# disciples_v1.net
KiCad netlist of a schematic drawn in EAGLE
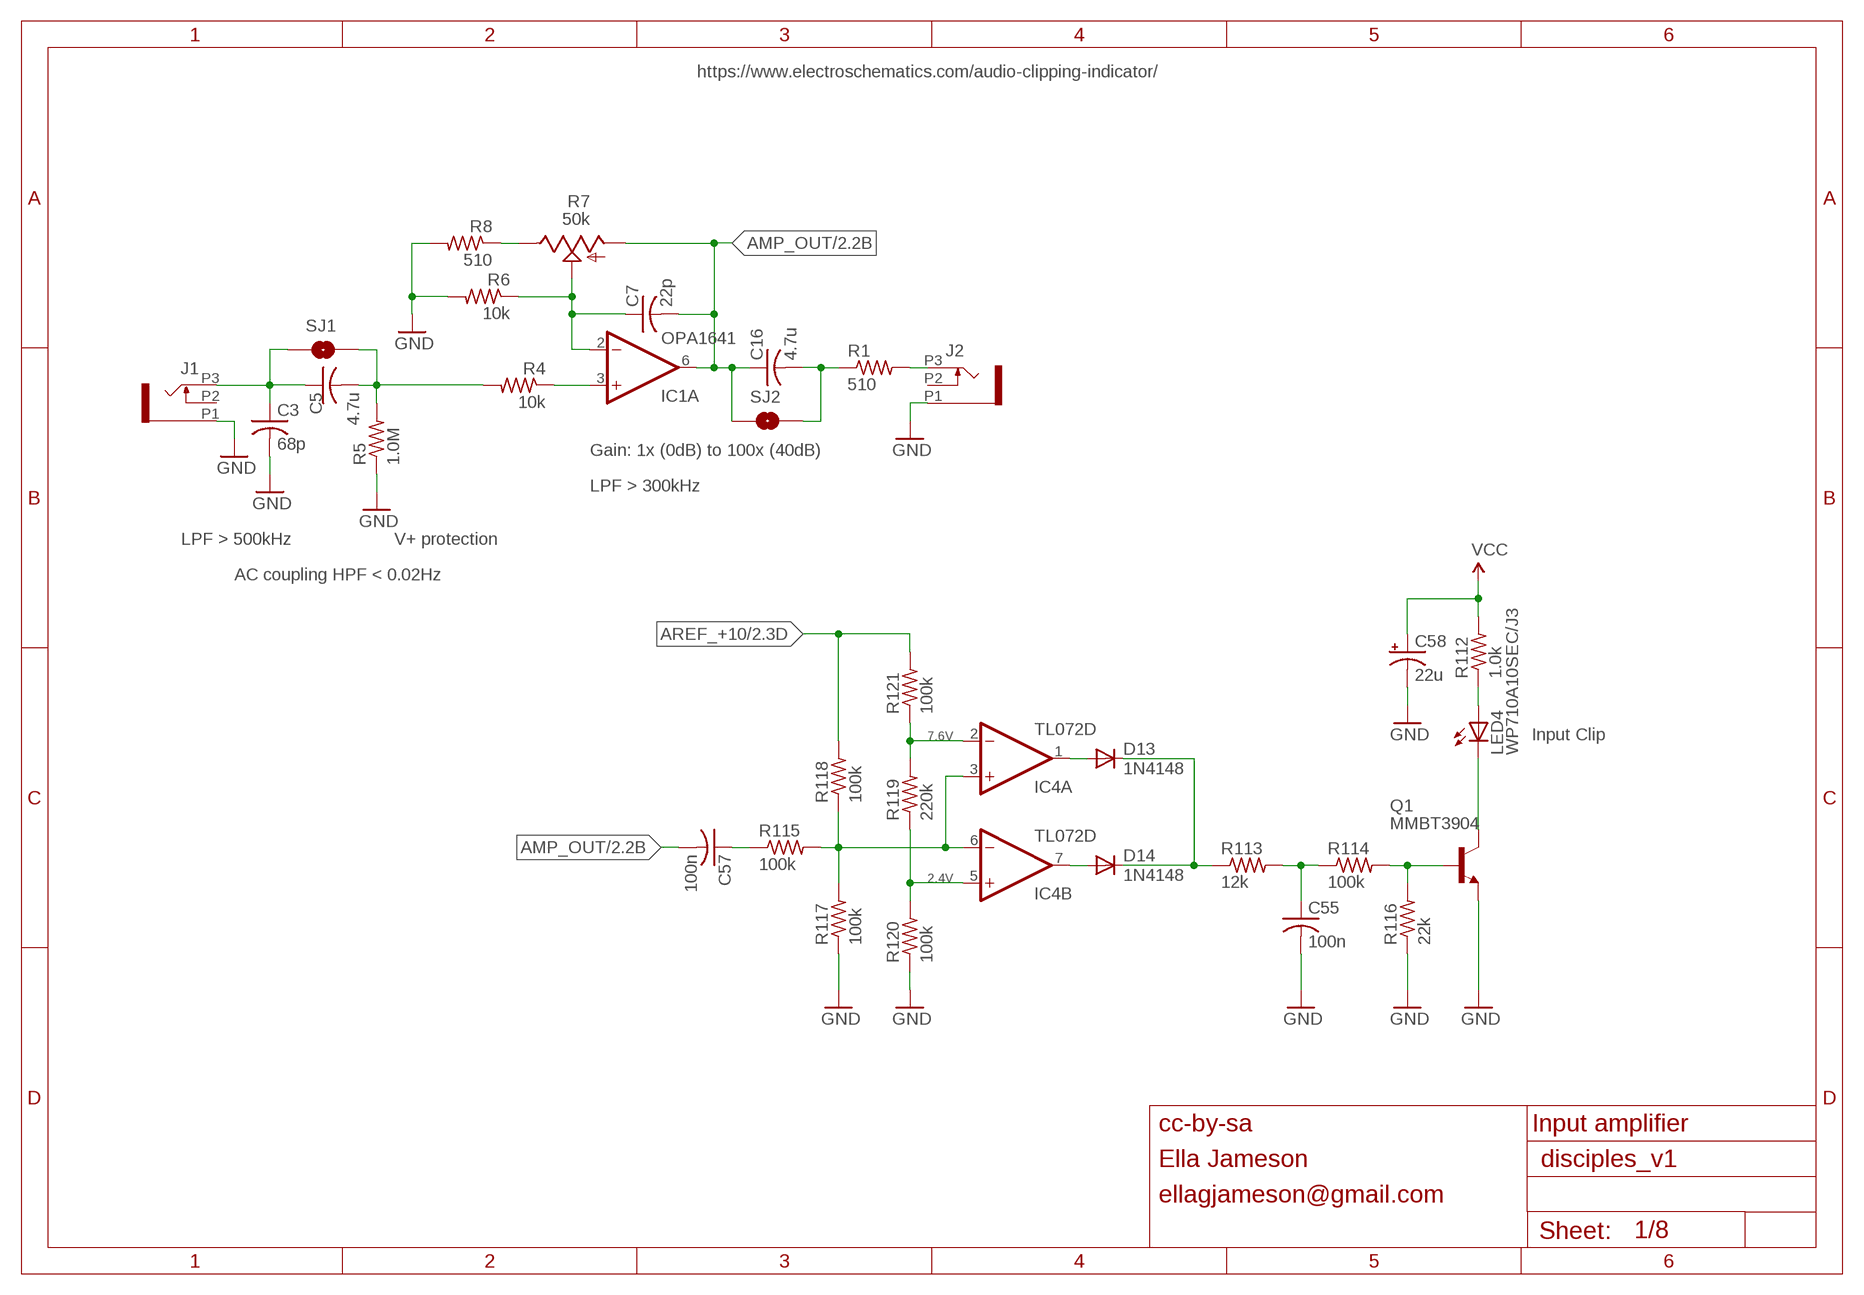
[diagram p0: schematic, sheet 1]
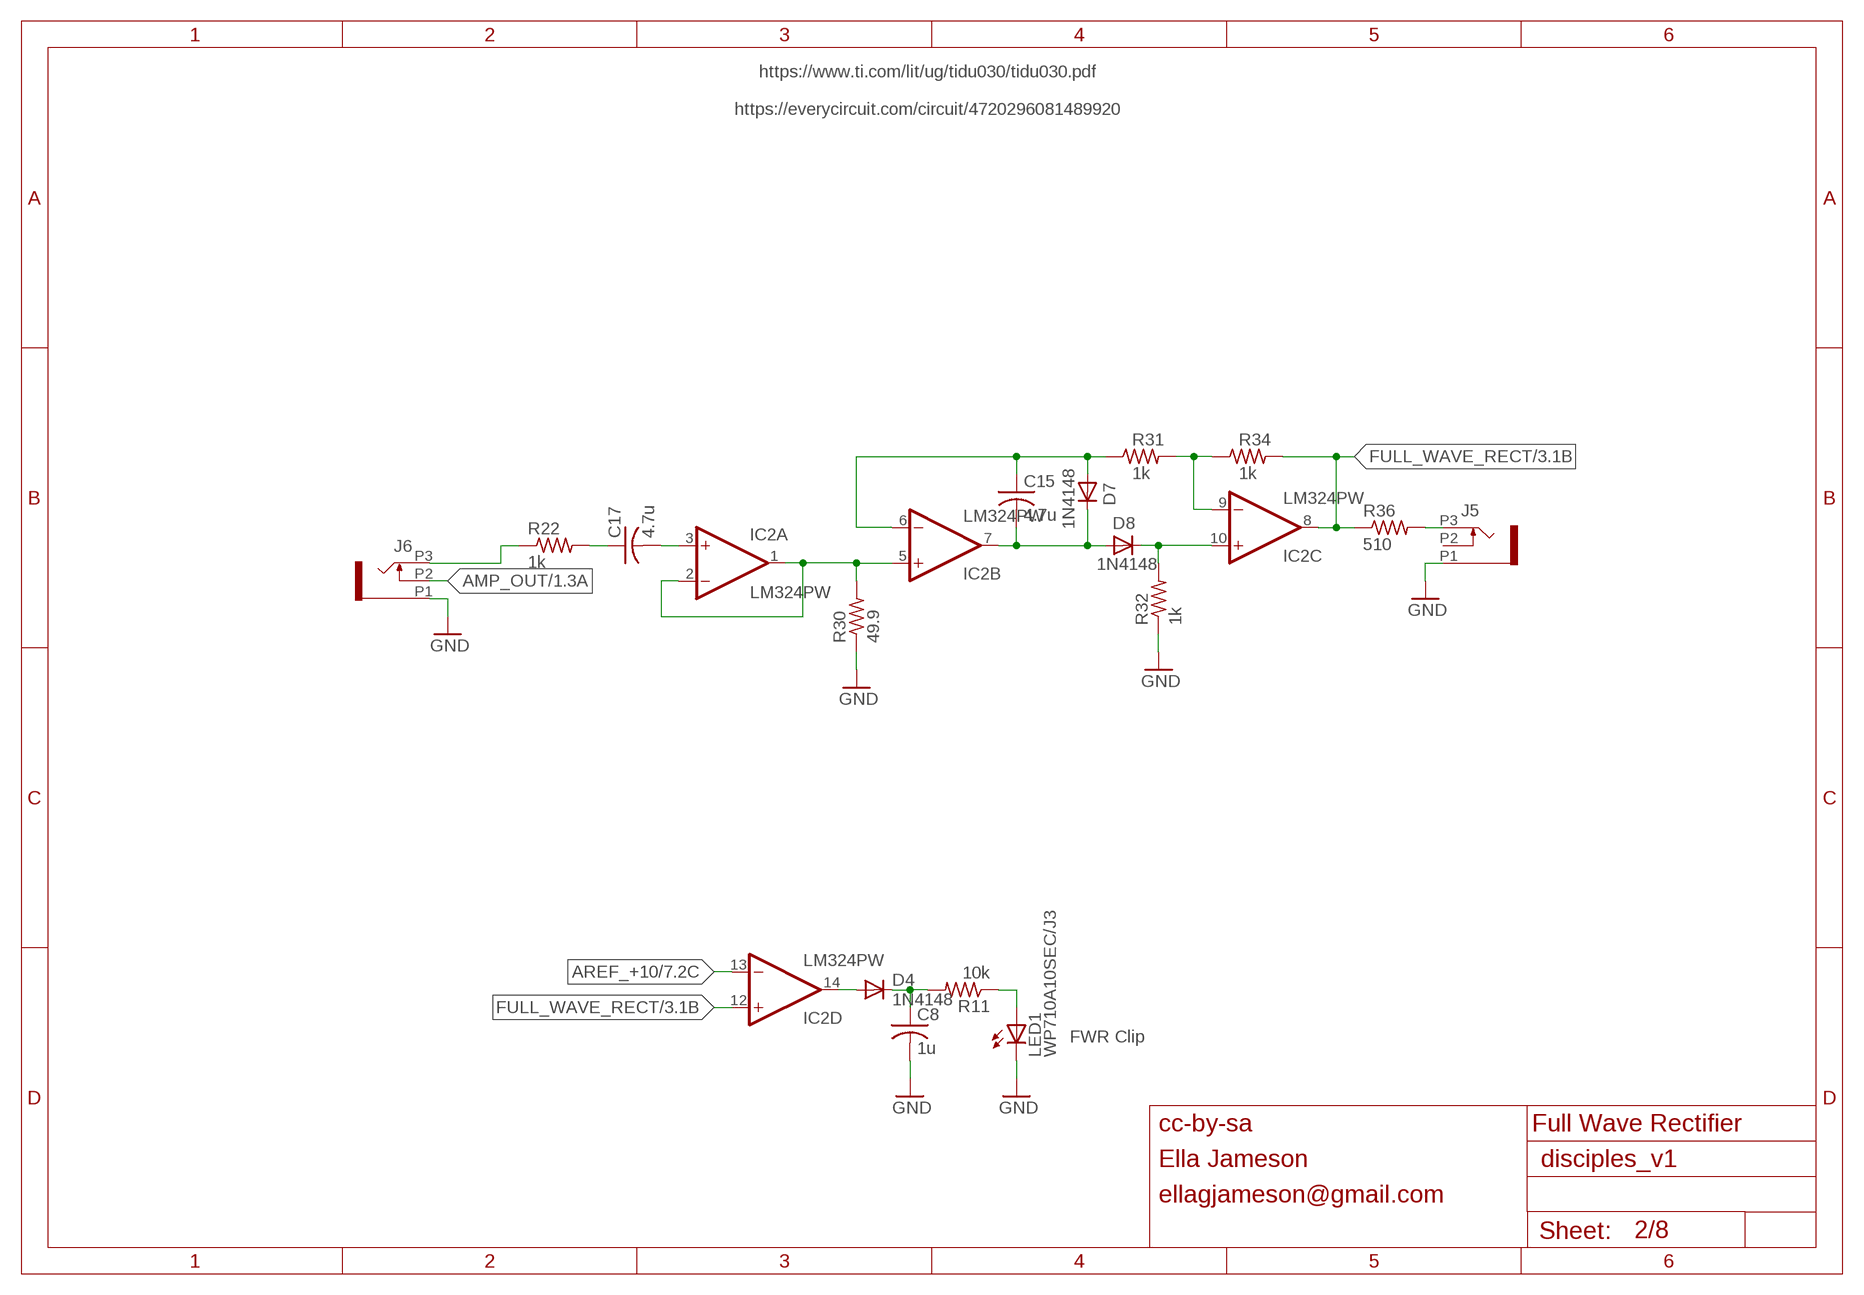
[diagram p1: schematic, sheet 2]
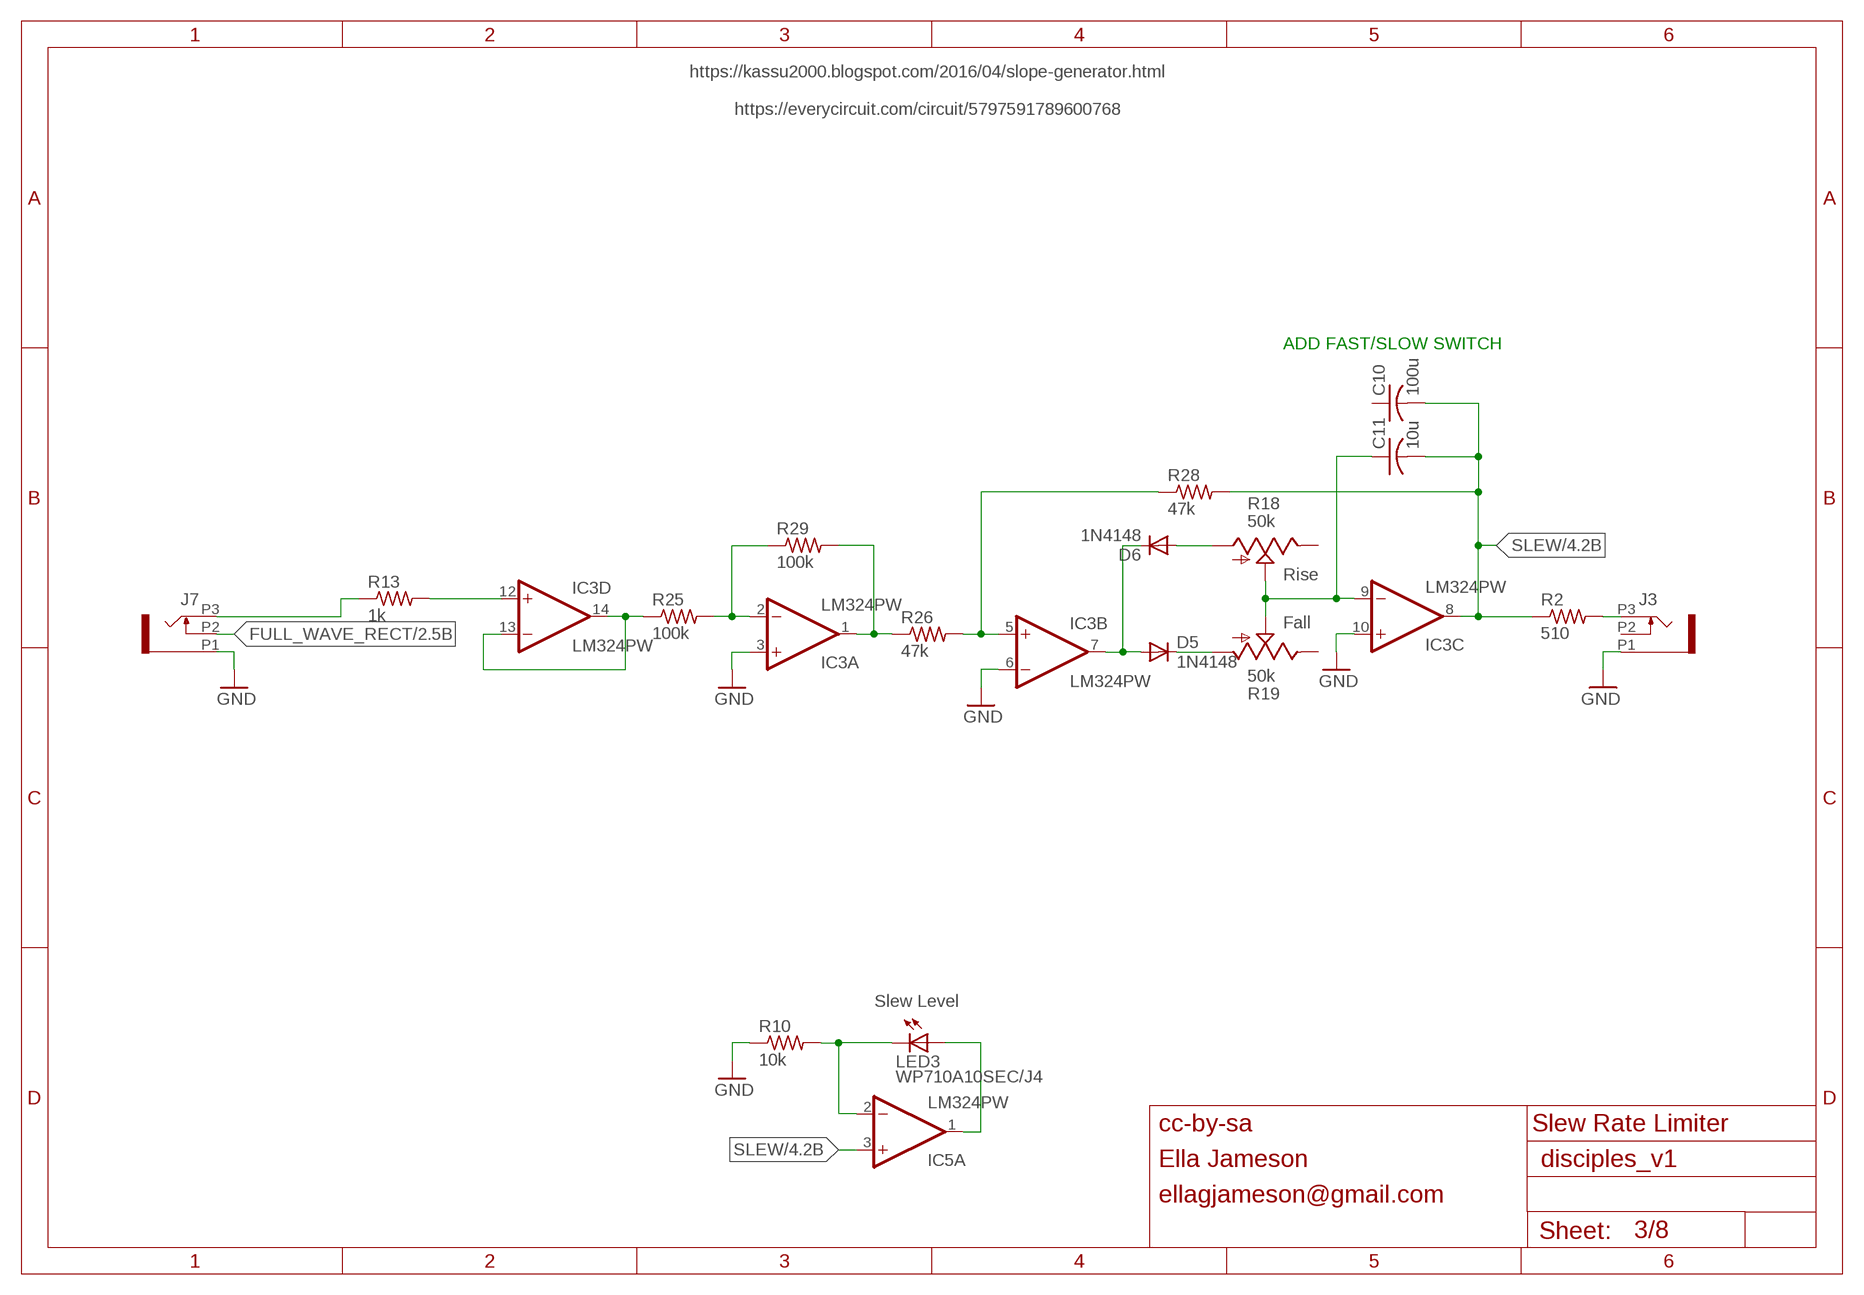
[diagram p2: schematic, sheet 3]
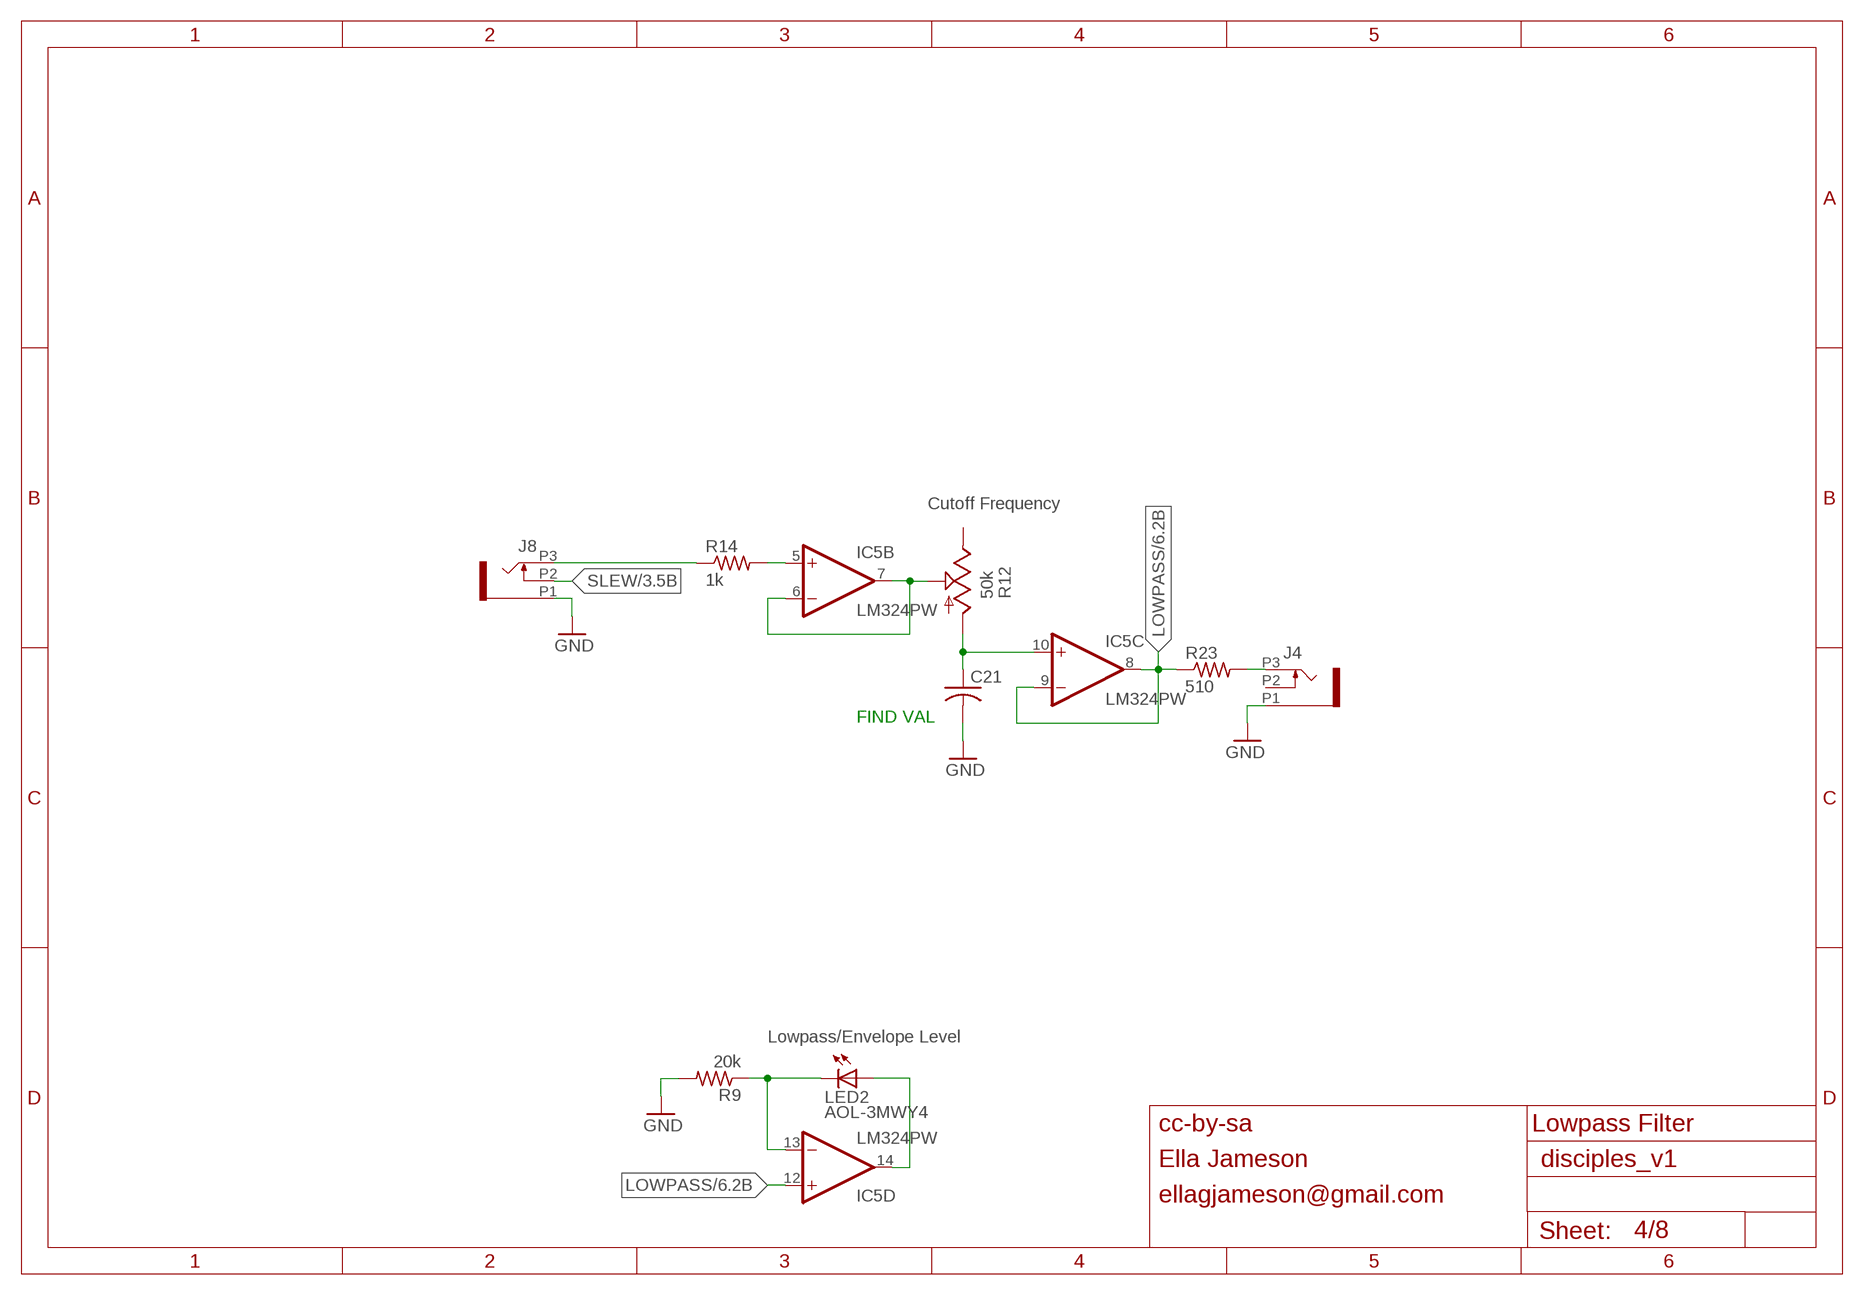
[diagram p3: schematic, sheet 4]
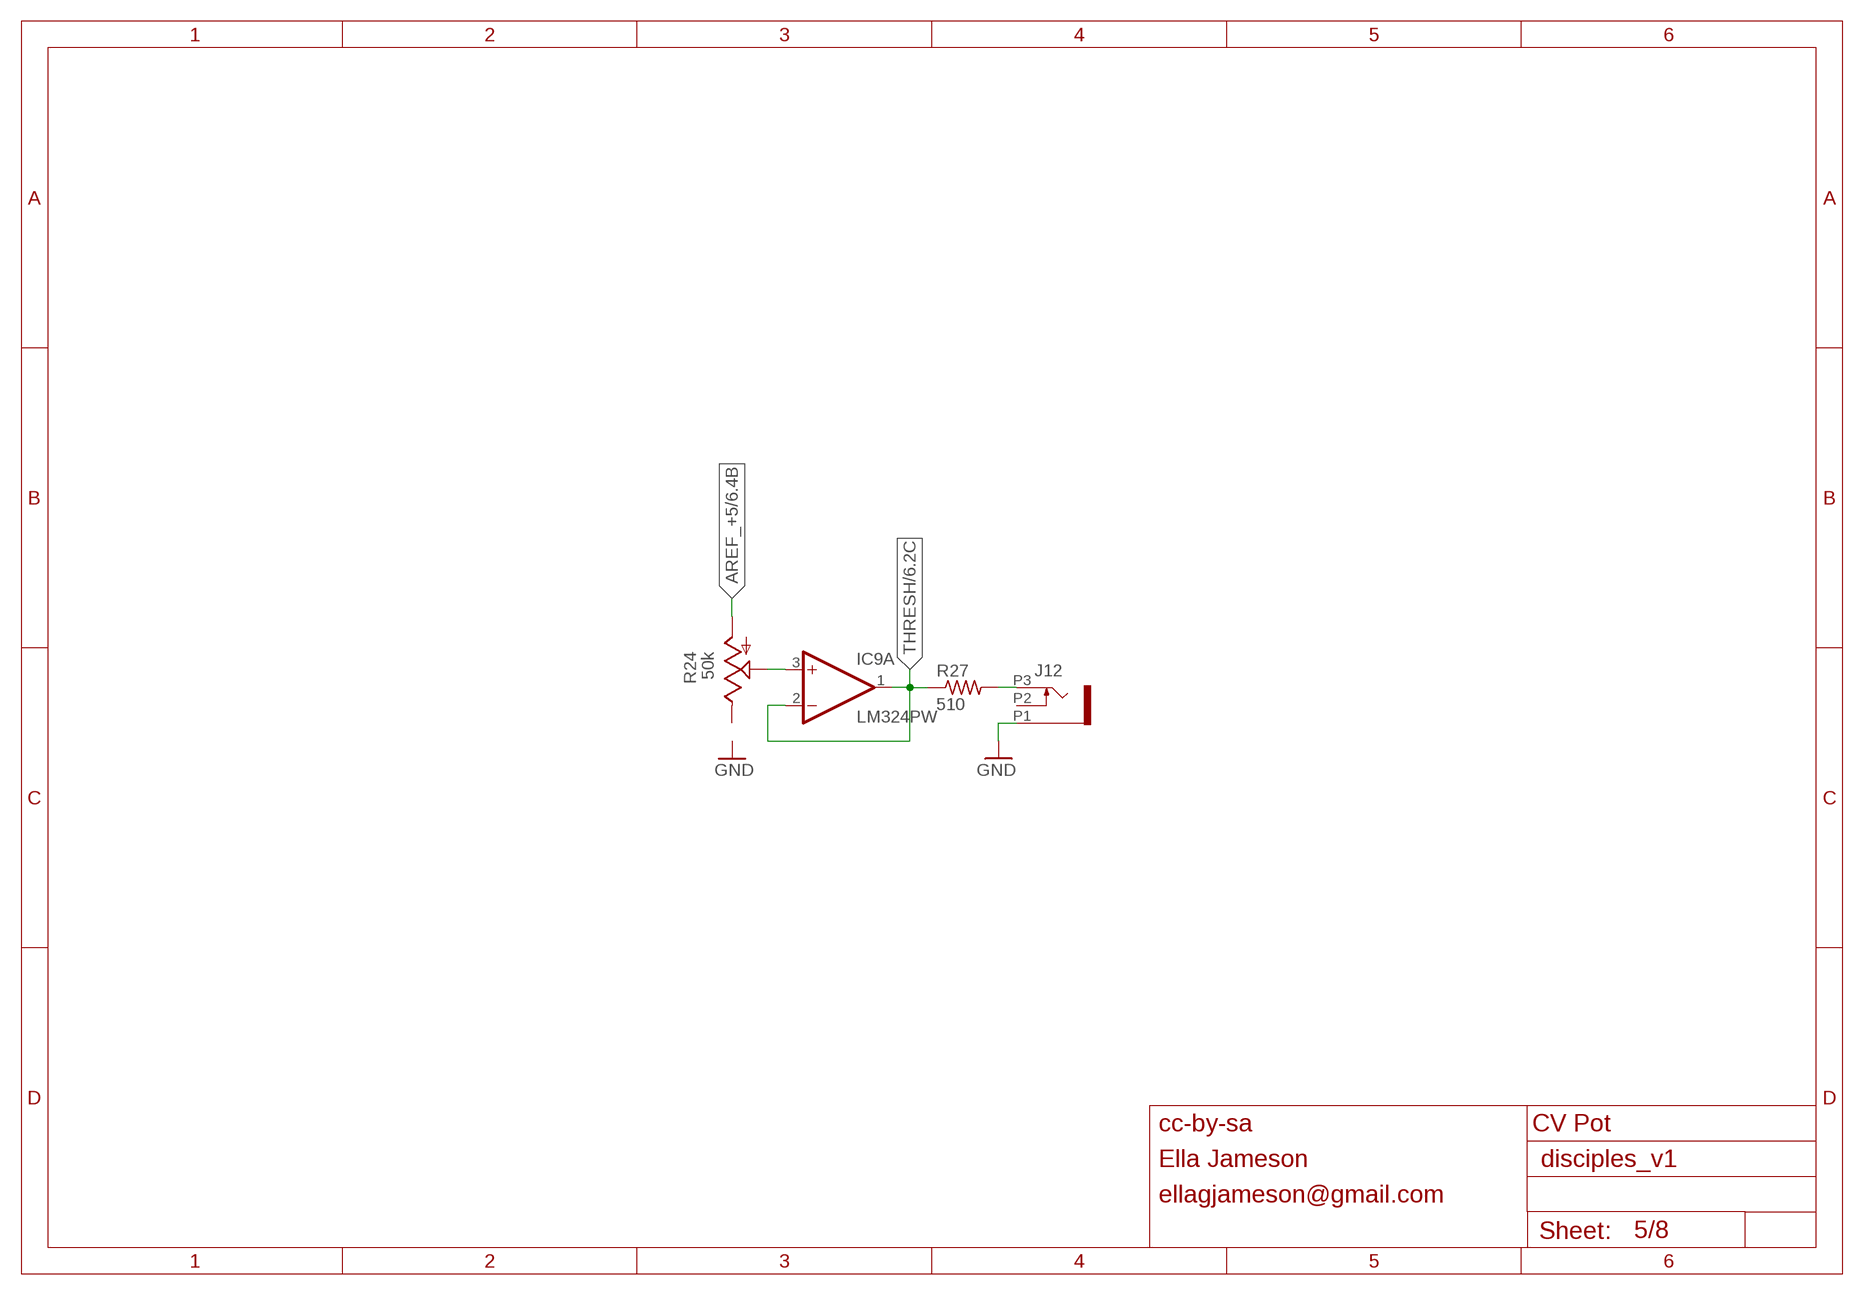
[diagram p4: schematic, sheet 5]
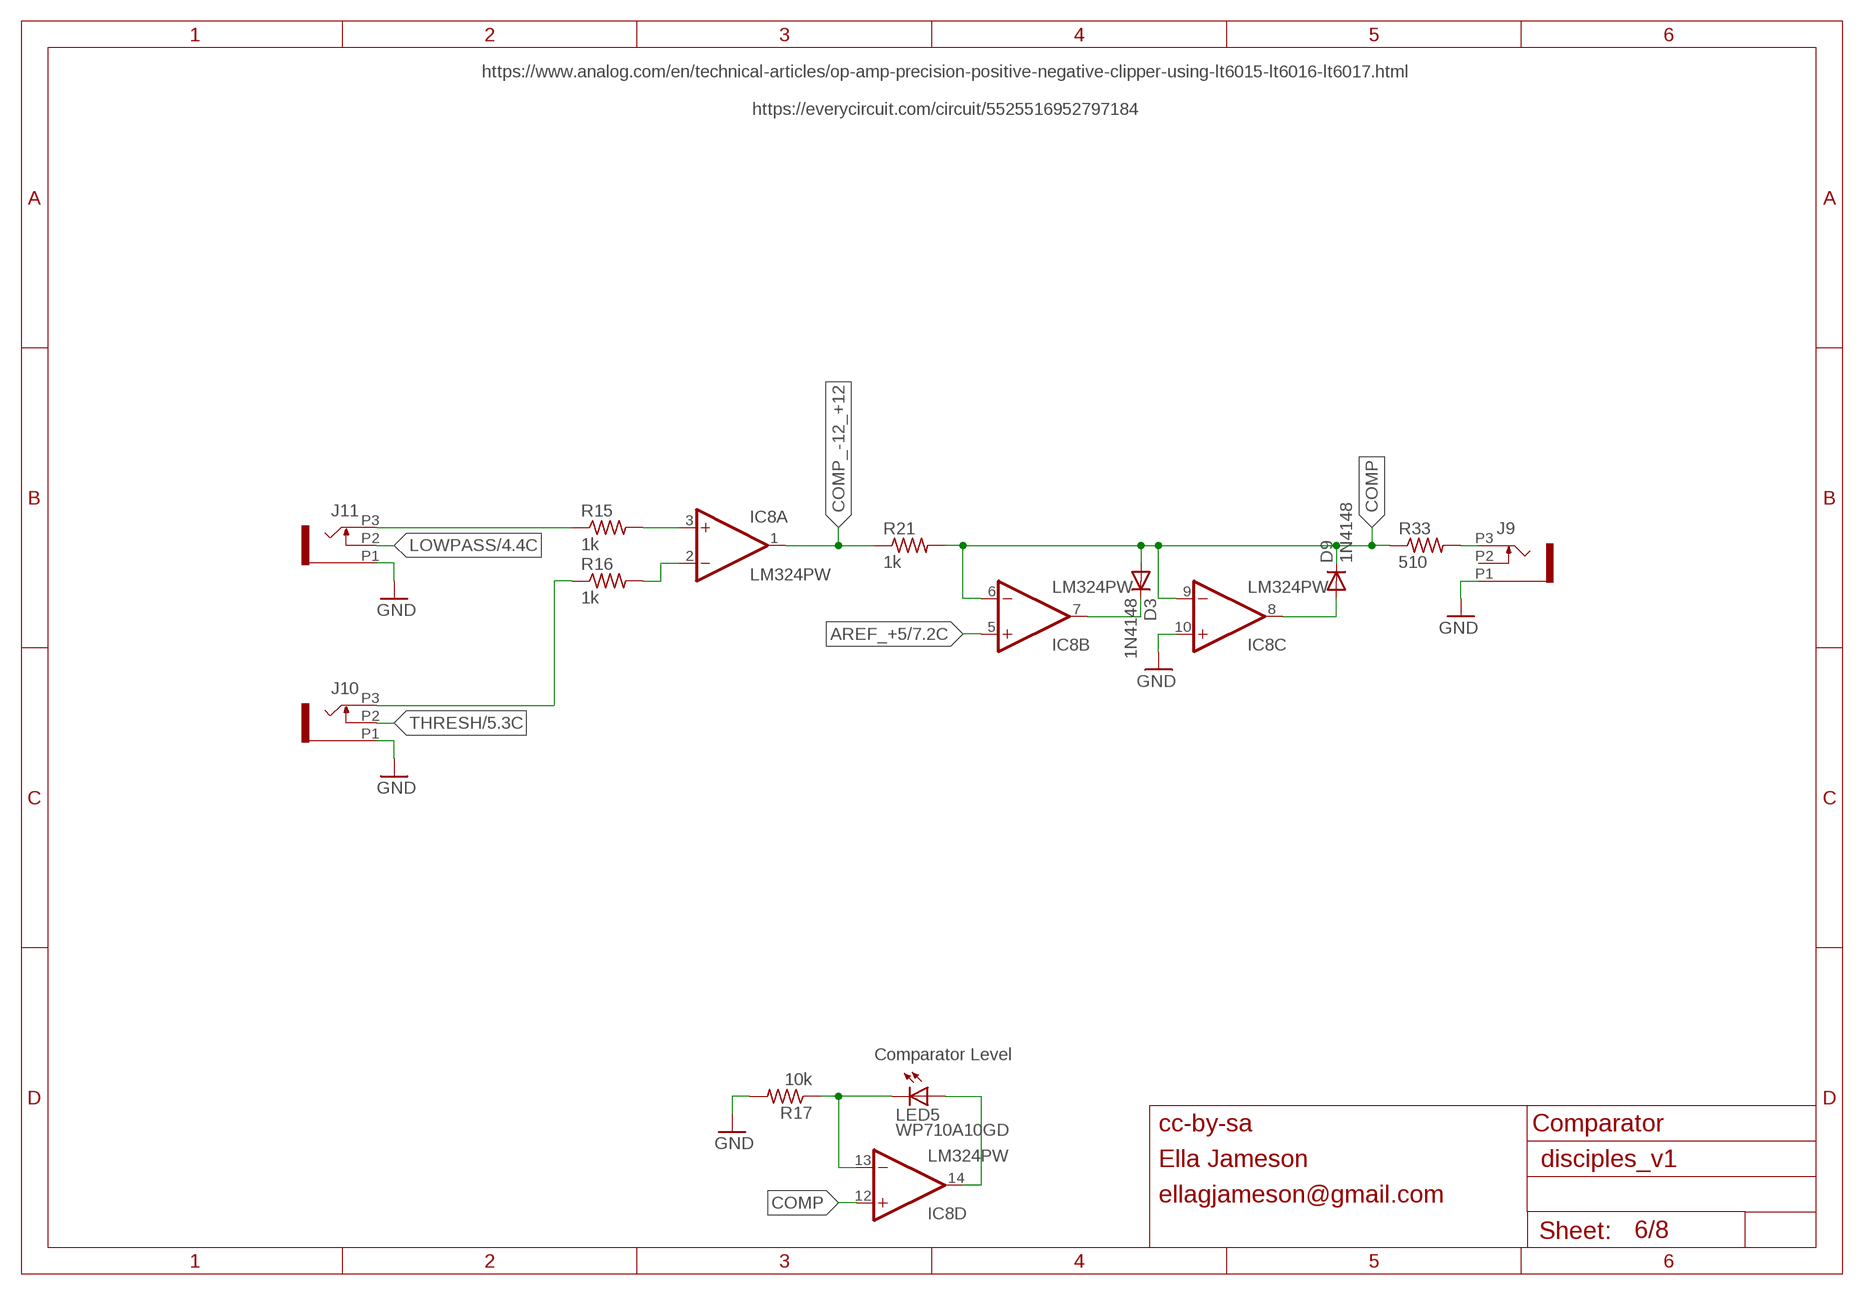
[diagram p5: schematic, sheet 6]
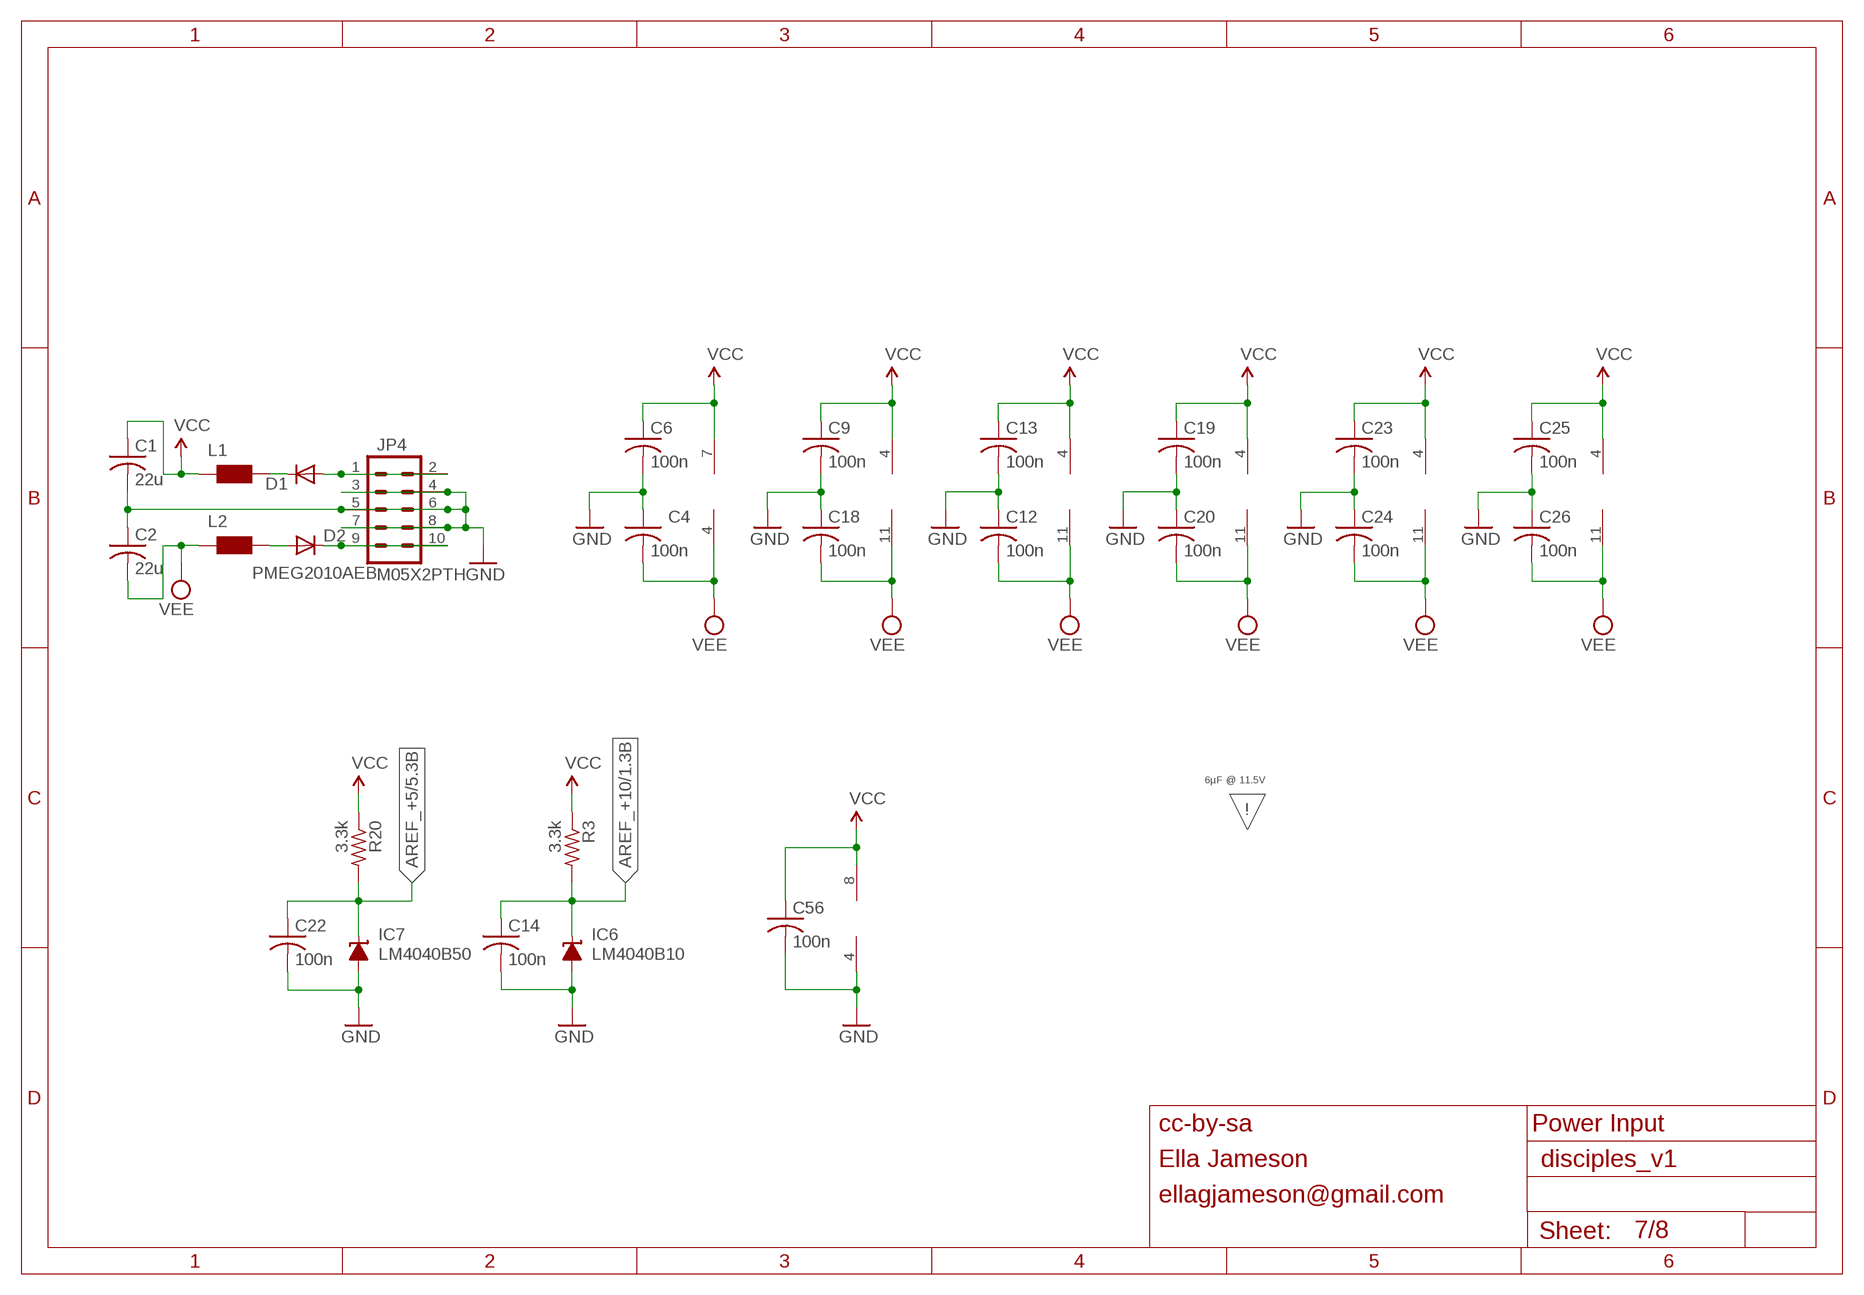
[diagram p6: schematic, sheet 7]
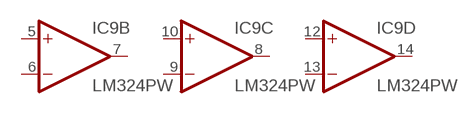
[diagram p7: schematic, sheet 8]

(export (version "E")
  (design (tool "Eeschema 10.0.6"))
  (components
    (comp (ref "C21")
      (value "C-USC0402")
      (footprint "eagle-import:C0402")
      (libsource (lib "eagle-import") (part "C-USC0402"))
    )
    (comp (ref "IC5")
      (value "LM324PW")
      (footprint "eagle-import:TSSOP14")
      (libsource (lib "eagle-import") (part "LM324PW"))
    )
    (comp (ref "J4")
      (value "PJ301_THONKICONN6")
      (footprint "eagle-import:WQP_PJ_301M6")
      (libsource (lib "eagle-import") (part "PJ301_THONKICONN6"))
    )
    (comp (ref "J8")
      (value "PJ301_THONKICONN6")
      (footprint "eagle-import:WQP_PJ_301M6")
      (libsource (lib "eagle-import") (part "PJ301_THONKICONN6"))
    )
    (comp (ref "LED2")
      (value "AOL-3MWY4")
      (footprint "eagle-import:LED3MM")
      (libsource (lib "eagle-import") (part "LED3MM"))
    )
    (comp (ref "R9")
      (value "20k")
      (footprint "eagle-import:R0402")
      (libsource (lib "eagle-import") (part "R-US_R0402"))
    )
    (comp (ref "R12")
      (value "50k")
      (footprint "eagle-import:ALPS_POT_VERTICAL_PS")
      (libsource (lib "eagle-import") (part "POT_USVERTICAL_PS"))
    )
    (comp (ref "R14")
      (value "1k")
      (footprint "eagle-import:R0402")
      (libsource (lib "eagle-import") (part "R-US_R0402"))
    )
    (comp (ref "R23")
      (value "510")
      (footprint "eagle-import:R0402")
      (libsource (lib "eagle-import") (part "R-US_R0402"))
    )
    (comp (ref "C8")
      (value "1u")
      (footprint "eagle-import:C0402")
      (libsource (lib "eagle-import") (part "C-USC0402"))
    )
    (comp (ref "C15")
      (value "4.7u")
      (footprint "eagle-import:C0603")
      (libsource (lib "eagle-import") (part "C-USC0603"))
    )
    (comp (ref "C17")
      (value "4.7u")
      (footprint "eagle-import:C0603")
      (libsource (lib "eagle-import") (part "C-USC0603"))
    )
    (comp (ref "D4")
      (value "1N4148")
      (footprint "eagle-import:SOD523")
      (libsource (lib "eagle-import") (part "DIODE-SOD523"))
    )
    (comp (ref "D7")
      (value "1N4148")
      (footprint "eagle-import:SOD523")
      (libsource (lib "eagle-import") (part "DIODE-SOD523"))
    )
    (comp (ref "D8")
      (value "1N4148")
      (footprint "eagle-import:SOD523")
      (libsource (lib "eagle-import") (part "DIODE-SOD523"))
    )
    (comp (ref "IC2")
      (value "LM324PW")
      (footprint "eagle-import:TSSOP14")
      (libsource (lib "eagle-import") (part "LM324PW"))
    )
    (comp (ref "J5")
      (value "PJ301_THONKICONN6")
      (footprint "eagle-import:WQP_PJ_301M6")
      (libsource (lib "eagle-import") (part "PJ301_THONKICONN6"))
    )
    (comp (ref "J6")
      (value "PJ301_THONKICONN6")
      (footprint "eagle-import:WQP_PJ_301M6")
      (libsource (lib "eagle-import") (part "PJ301_THONKICONN6"))
    )
    (comp (ref "LED1")
      (value "WP710A10SEC/J3")
      (footprint "eagle-import:LED3MM")
      (libsource (lib "eagle-import") (part "LED3MM"))
    )
    (comp (ref "R11")
      (value "10k")
      (footprint "eagle-import:R0402")
      (libsource (lib "eagle-import") (part "R-US_R0402"))
    )
    (comp (ref "R22")
      (value "1k")
      (footprint "eagle-import:R0402")
      (libsource (lib "eagle-import") (part "R-US_R0402"))
    )
    (comp (ref "R30")
      (value "49.9")
      (footprint "eagle-import:R0402")
      (libsource (lib "eagle-import") (part "R-US_R0402"))
    )
    (comp (ref "R31")
      (value "1k")
      (footprint "eagle-import:R0402")
      (libsource (lib "eagle-import") (part "R-US_R0402"))
    )
    (comp (ref "R32")
      (value "1k")
      (footprint "eagle-import:R0402")
      (libsource (lib "eagle-import") (part "R-US_R0402"))
    )
    (comp (ref "R34")
      (value "1k")
      (footprint "eagle-import:R0402")
      (libsource (lib "eagle-import") (part "R-US_R0402"))
    )
    (comp (ref "R36")
      (value "510")
      (footprint "eagle-import:R0402")
      (libsource (lib "eagle-import") (part "R-US_R0402"))
    )
    (comp (ref "C1")
      (value "22u")
      (footprint "eagle-import:C1206")
      (libsource (lib "eagle-import") (part "C-USC1206"))
    )
    (comp (ref "C2")
      (value "22u")
      (footprint "eagle-import:C1206")
      (libsource (lib "eagle-import") (part "C-USC1206"))
    )
    (comp (ref "C4")
      (value "100n")
      (footprint "eagle-import:C0402")
      (libsource (lib "eagle-import") (part "C-USC0402"))
    )
    (comp (ref "C6")
      (value "100n")
      (footprint "eagle-import:C0402")
      (libsource (lib "eagle-import") (part "C-USC0402"))
    )
    (comp (ref "C9")
      (value "100n")
      (footprint "eagle-import:C0402")
      (libsource (lib "eagle-import") (part "C-USC0402"))
    )
    (comp (ref "C12")
      (value "100n")
      (footprint "eagle-import:C0402")
      (libsource (lib "eagle-import") (part "C-USC0402"))
    )
    (comp (ref "C13")
      (value "100n")
      (footprint "eagle-import:C0402")
      (libsource (lib "eagle-import") (part "C-USC0402"))
    )
    (comp (ref "C14")
      (value "100n")
      (footprint "eagle-import:C0603")
      (libsource (lib "eagle-import") (part "C-USC0603"))
    )
    (comp (ref "C18")
      (value "100n")
      (footprint "eagle-import:C0402")
      (libsource (lib "eagle-import") (part "C-USC0402"))
    )
    (comp (ref "C19")
      (value "100n")
      (footprint "eagle-import:C0402")
      (libsource (lib "eagle-import") (part "C-USC0402"))
    )
    (comp (ref "C20")
      (value "100n")
      (footprint "eagle-import:C0402")
      (libsource (lib "eagle-import") (part "C-USC0402"))
    )
    (comp (ref "C22")
      (value "100n")
      (footprint "eagle-import:C0603")
      (libsource (lib "eagle-import") (part "C-USC0603"))
    )
    (comp (ref "C23")
      (value "100n")
      (footprint "eagle-import:C0402")
      (libsource (lib "eagle-import") (part "C-USC0402"))
    )
    (comp (ref "C24")
      (value "100n")
      (footprint "eagle-import:C0402")
      (libsource (lib "eagle-import") (part "C-USC0402"))
    )
    (comp (ref "C25")
      (value "100n")
      (footprint "eagle-import:C0402")
      (libsource (lib "eagle-import") (part "C-USC0402"))
    )
    (comp (ref "C26")
      (value "100n")
      (footprint "eagle-import:C0402")
      (libsource (lib "eagle-import") (part "C-USC0402"))
    )
    (comp (ref "C56")
      (value "100n")
      (footprint "eagle-import:C0603")
      (libsource (lib "eagle-import") (part "C-USC0603"))
    )
    (comp (ref "D1")
      (value "PMEG2010AEB")
      (footprint "eagle-import:SOD523")
      (libsource (lib "eagle-import") (part "DIODE-SOD523"))
    )
    (comp (ref "D2")
      (value "PMEG2010AEB")
      (footprint "eagle-import:SOD523")
      (libsource (lib "eagle-import") (part "DIODE-SOD523"))
    )
    (comp (ref "IC1")
      (value "OPA1641")
      (footprint "eagle-import:MSOP8")
      (libsource (lib "eagle-import") (part "OPA1641"))
    )
    (comp (ref "IC3")
      (value "LM324PW")
      (footprint "eagle-import:TSSOP14")
      (libsource (lib "eagle-import") (part "LM324PW"))
    )
    (comp (ref "IC4")
      (value "TL072D")
      (footprint "eagle-import:SO08")
      (libsource (lib "eagle-import") (part "TL072D"))
    )
    (comp (ref "IC6")
      (value "LM4040B10")
      (footprint "eagle-import:DBZ_R-PDSO-G3")
      (libsource (lib "eagle-import") (part "LM4041DBZB12"))
    )
    (comp (ref "IC7")
      (value "LM4040B50")
      (footprint "eagle-import:DBZ_R-PDSO-G3")
      (libsource (lib "eagle-import") (part "LM4041DBZB12"))
    )
    (comp (ref "IC8")
      (value "LM324PW")
      (footprint "eagle-import:TSSOP14")
      (libsource (lib "eagle-import") (part "LM324PW"))
    )
    (comp (ref "IC9")
      (value "LM324PW")
      (footprint "eagle-import:TSSOP14")
      (libsource (lib "eagle-import") (part "LM324PW"))
    )
    (comp (ref "JP4")
      (value "M05X2PTH")
      (footprint "eagle-import:AVR_ICSP")
      (libsource (lib "eagle-import") (part "M05X2PTH"))
    )
    (comp (ref "L1")
      (value "WE-CBF_0603")
      (footprint "eagle-import:0603")
      (libsource (lib "eagle-import") (part "WE-CBF_0603"))
    )
    (comp (ref "L2")
      (value "WE-CBF_0603")
      (footprint "eagle-import:0603")
      (libsource (lib "eagle-import") (part "WE-CBF_0603"))
    )
    (comp (ref "R3")
      (value "3.3k")
      (footprint "eagle-import:R0603")
      (libsource (lib "eagle-import") (part "R-US_R0603"))
    )
    (comp (ref "R20")
      (value "3.3k")
      (footprint "eagle-import:R0603")
      (libsource (lib "eagle-import") (part "R-US_R0603"))
    )
    (comp (ref "J12")
      (value "PJ301_THONKICONN6")
      (footprint "eagle-import:WQP_PJ_301M6")
      (libsource (lib "eagle-import") (part "PJ301_THONKICONN6"))
    )
    (comp (ref "R24")
      (value "50k")
      (footprint "eagle-import:ALPS_POT_VERTICAL_PS")
      (libsource (lib "eagle-import") (part "POT_USVERTICAL_PS"))
    )
    (comp (ref "R27")
      (value "510")
      (footprint "eagle-import:R0402")
      (libsource (lib "eagle-import") (part "R-US_R0402"))
    )
    (comp (ref "C3")
      (value "68p")
      (footprint "eagle-import:C0402")
      (libsource (lib "eagle-import") (part "C-USC0402"))
    )
    (comp (ref "C5")
      (value "4.7u")
      (footprint "eagle-import:C0603")
      (libsource (lib "eagle-import") (part "C-USC0603"))
    )
    (comp (ref "C7")
      (value "22p")
      (footprint "eagle-import:C0402")
      (libsource (lib "eagle-import") (part "C-USC0402"))
    )
    (comp (ref "C16")
      (value "4.7u")
      (footprint "eagle-import:C0603")
      (libsource (lib "eagle-import") (part "C-USC0603"))
    )
    (comp (ref "C55")
      (value "100n")
      (footprint "eagle-import:C0603")
      (libsource (lib "eagle-import") (part "C-USC0603"))
    )
    (comp (ref "C57")
      (value "100n")
      (footprint "eagle-import:C0603")
      (libsource (lib "eagle-import") (part "C-USC0603"))
    )
    (comp (ref "C58")
      (value "22u")
      (footprint "eagle-import:PANASONIC_C")
      (libsource (lib "eagle-import") (part "CPOL-USC"))
    )
    (comp (ref "D13")
      (value "1N4148")
      (footprint "eagle-import:SOD323-W")
      (libsource (lib "eagle-import") (part "DIODE-SOD323-W"))
    )
    (comp (ref "D14")
      (value "1N4148")
      (footprint "eagle-import:SOD323-W")
      (libsource (lib "eagle-import") (part "DIODE-SOD323-W"))
    )
    (comp (ref "J1")
      (value "PJ301_THONKICONN6")
      (footprint "eagle-import:WQP_PJ_301M6")
      (libsource (lib "eagle-import") (part "PJ301_THONKICONN6"))
    )
    (comp (ref "J2")
      (value "PJ301_THONKICONN6")
      (footprint "eagle-import:WQP_PJ_301M6")
      (libsource (lib "eagle-import") (part "PJ301_THONKICONN6"))
    )
    (comp (ref "LED4")
      (value "WP710A10SEC/J3")
      (footprint "eagle-import:LED3MM")
      (libsource (lib "eagle-import") (part "LED3MM"))
    )
    (comp (ref "Q1")
      (value "MMBT3904")
      (footprint "eagle-import:SOT23-BEC")
      (libsource (lib "eagle-import") (part "-NPN-SOT23-BECMMBT3904LT1"))
    )
    (comp (ref "R1")
      (value "510")
      (footprint "eagle-import:R0402")
      (libsource (lib "eagle-import") (part "R-US_R0402"))
    )
    (comp (ref "R4")
      (value "10k")
      (footprint "eagle-import:R0402")
      (libsource (lib "eagle-import") (part "R-US_R0402"))
    )
    (comp (ref "R5")
      (value "1.0M")
      (footprint "eagle-import:R0402")
      (libsource (lib "eagle-import") (part "R-US_R0402"))
    )
    (comp (ref "R6")
      (value "10k")
      (footprint "eagle-import:R0402")
      (libsource (lib "eagle-import") (part "R-US_R0402"))
    )
    (comp (ref "R7")
      (value "50k")
      (footprint "eagle-import:ALPS_POT_VERTICAL_PS")
      (libsource (lib "eagle-import") (part "POT_USVERTICAL_PS"))
    )
    (comp (ref "R8")
      (value "510")
      (footprint "eagle-import:R0402")
      (libsource (lib "eagle-import") (part "R-US_R0402"))
    )
    (comp (ref "R112")
      (value "1.0k")
      (footprint "eagle-import:R0603")
      (libsource (lib "eagle-import") (part "R-US_R0603"))
    )
    (comp (ref "R113")
      (value "12k")
      (footprint "eagle-import:R0603")
      (libsource (lib "eagle-import") (part "R-US_R0603"))
    )
    (comp (ref "R114")
      (value "100k")
      (footprint "eagle-import:R0603")
      (libsource (lib "eagle-import") (part "R-US_R0603"))
    )
    (comp (ref "R115")
      (value "100k")
      (footprint "eagle-import:R0603")
      (libsource (lib "eagle-import") (part "R-US_R0603"))
    )
    (comp (ref "R116")
      (value "22k")
      (footprint "eagle-import:R0603")
      (libsource (lib "eagle-import") (part "R-US_R0603"))
    )
    (comp (ref "R117")
      (value "100k")
      (footprint "eagle-import:R0603")
      (libsource (lib "eagle-import") (part "R-US_R0603"))
    )
    (comp (ref "R118")
      (value "100k")
      (footprint "eagle-import:R0603")
      (libsource (lib "eagle-import") (part "R-US_R0603"))
    )
    (comp (ref "R119")
      (value "220k")
      (footprint "eagle-import:R0603")
      (libsource (lib "eagle-import") (part "R-US_R0603"))
    )
    (comp (ref "R120")
      (value "100k")
      (footprint "eagle-import:R0603")
      (libsource (lib "eagle-import") (part "R-US_R0603"))
    )
    (comp (ref "R121")
      (value "100k")
      (footprint "eagle-import:R0603")
      (libsource (lib "eagle-import") (part "R-US_R0603"))
    )
    (comp (ref "SJ1")
      (value "SOLDERJUMPERNC")
      (footprint "eagle-import:SJ_2S")
      (libsource (lib "eagle-import") (part "SOLDERJUMPERNC"))
    )
    (comp (ref "SJ2")
      (value "SOLDERJUMPERNC")
      (footprint "eagle-import:SJ_2S")
      (libsource (lib "eagle-import") (part "SOLDERJUMPERNC"))
    )
    (comp (ref "C10")
      (value "100u")
      (footprint "eagle-import:C0402")
      (libsource (lib "eagle-import") (part "C-USC0402"))
    )
    (comp (ref "C11")
      (value "10u")
      (footprint "eagle-import:C0402")
      (libsource (lib "eagle-import") (part "C-USC0402"))
    )
    (comp (ref "D5")
      (value "1N4148")
      (footprint "eagle-import:SOD523")
      (libsource (lib "eagle-import") (part "DIODE-SOD523"))
    )
    (comp (ref "D6")
      (value "1N4148")
      (footprint "eagle-import:SOD523")
      (libsource (lib "eagle-import") (part "DIODE-SOD523"))
    )
    (comp (ref "J3")
      (value "PJ301_THONKICONN6")
      (footprint "eagle-import:WQP_PJ_301M6")
      (libsource (lib "eagle-import") (part "PJ301_THONKICONN6"))
    )
    (comp (ref "J7")
      (value "PJ301_THONKICONN6")
      (footprint "eagle-import:WQP_PJ_301M6")
      (libsource (lib "eagle-import") (part "PJ301_THONKICONN6"))
    )
    (comp (ref "LED3")
      (value "WP710A10SEC/J4")
      (footprint "eagle-import:LED3MM")
      (libsource (lib "eagle-import") (part "LED3MM"))
    )
    (comp (ref "R2")
      (value "510")
      (footprint "eagle-import:R0402")
      (libsource (lib "eagle-import") (part "R-US_R0402"))
    )
    (comp (ref "R10")
      (value "10k")
      (footprint "eagle-import:R0402")
      (libsource (lib "eagle-import") (part "R-US_R0402"))
    )
    (comp (ref "R13")
      (value "1k")
      (footprint "eagle-import:R0402")
      (libsource (lib "eagle-import") (part "R-US_R0402"))
    )
    (comp (ref "R18")
      (value "50k")
      (footprint "eagle-import:ALPS_POT_VERTICAL_PS")
      (libsource (lib "eagle-import") (part "POT_USVERTICAL_PS"))
    )
    (comp (ref "R19")
      (value "50k")
      (footprint "eagle-import:ALPS_POT_VERTICAL_PS")
      (libsource (lib "eagle-import") (part "POT_USVERTICAL_PS"))
    )
    (comp (ref "R25")
      (value "100k")
      (footprint "eagle-import:R0402")
      (libsource (lib "eagle-import") (part "R-US_R0402"))
    )
    (comp (ref "R26")
      (value "47k")
      (footprint "eagle-import:R0402")
      (libsource (lib "eagle-import") (part "R-US_R0402"))
    )
    (comp (ref "R28")
      (value "47k")
      (footprint "eagle-import:R0402")
      (libsource (lib "eagle-import") (part "R-US_R0402"))
    )
    (comp (ref "R29")
      (value "100k")
      (footprint "eagle-import:R0402")
      (libsource (lib "eagle-import") (part "R-US_R0402"))
    )
    (comp (ref "D3")
      (value "1N4148")
      (footprint "eagle-import:SOD523")
      (libsource (lib "eagle-import") (part "DIODE-SOD523"))
    )
    (comp (ref "D9")
      (value "1N4148")
      (footprint "eagle-import:SOD523")
      (libsource (lib "eagle-import") (part "DIODE-SOD523"))
    )
    (comp (ref "J9")
      (value "PJ301_THONKICONN6")
      (footprint "eagle-import:WQP_PJ_301M6")
      (libsource (lib "eagle-import") (part "PJ301_THONKICONN6"))
    )
    (comp (ref "J10")
      (value "PJ301_THONKICONN6")
      (footprint "eagle-import:WQP_PJ_301M6")
      (libsource (lib "eagle-import") (part "PJ301_THONKICONN6"))
    )
    (comp (ref "J11")
      (value "PJ301_THONKICONN6")
      (footprint "eagle-import:WQP_PJ_301M6")
      (libsource (lib "eagle-import") (part "PJ301_THONKICONN6"))
    )
    (comp (ref "LED5")
      (value "WP710A10GD")
      (footprint "eagle-import:LED3MM")
      (libsource (lib "eagle-import") (part "LED3MM"))
    )
    (comp (ref "R15")
      (value "1k")
      (footprint "eagle-import:R0402")
      (libsource (lib "eagle-import") (part "R-US_R0402"))
    )
    (comp (ref "R16")
      (value "1k")
      (footprint "eagle-import:R0402")
      (libsource (lib "eagle-import") (part "R-US_R0402"))
    )
    (comp (ref "R17")
      (value "10k")
      (footprint "eagle-import:R0402")
      (libsource (lib "eagle-import") (part "R-US_R0402"))
    )
    (comp (ref "R21")
      (value "1k")
      (footprint "eagle-import:R0402")
      (libsource (lib "eagle-import") (part "R-US_R0402"))
    )
    (comp (ref "R33")
      (value "510")
      (footprint "eagle-import:R0402")
      (libsource (lib "eagle-import") (part "R-US_R0402"))
    )
  )
  (nets
    (net (code "1") (name "AMP_OUT") (class "Default")
      (node (ref "C16") (pin "1") (pinfunction "1_1") (pintype "passive"))
      (node (ref "C57") (pin "2") (pinfunction "2_2") (pintype "passive"))
      (node (ref "C7") (pin "2") (pinfunction "2_2") (pintype "passive"))
      (node (ref "IC1") (pin "6") (pinfunction "OUT_6") (pintype "output"))
      (node (ref "J6") (pin "P2") (pinfunction "2_P2") (pintype "passive"))
      (node (ref "R7") (pin "P$3") (pinfunction "A_P$3") (pintype "passive"))
      (node (ref "SJ2") (pin "1") (pinfunction "1_1") (pintype "passive"))
    )
    (net (code "2") (name "AREF_+5") (class "Default")
      (node (ref "C22") (pin "1") (pinfunction "1_1") (pintype "passive"))
      (node (ref "IC7") (pin "1") (pinfunction "C_1") (pintype "passive"))
      (node (ref "IC8") (pin "5") (pinfunction "+IN_5") (pintype "input"))
      (node (ref "R20") (pin "2") (pinfunction "2_2") (pintype "passive"))
      (node (ref "R24") (pin "P$3") (pinfunction "A_P$3") (pintype "passive"))
    )
    (net (code "3") (name "AREF_+10") (class "Default")
      (node (ref "C14") (pin "1") (pinfunction "1_1") (pintype "passive"))
      (node (ref "IC2") (pin "13") (pinfunction "-IN_13") (pintype "input"))
      (node (ref "IC6") (pin "1") (pinfunction "C_1") (pintype "passive"))
      (node (ref "R118") (pin "2") (pinfunction "2_2") (pintype "passive"))
      (node (ref "R121") (pin "2") (pinfunction "2_2") (pintype "passive"))
      (node (ref "R3") (pin "2") (pinfunction "2_2") (pintype "passive"))
    )
    (net (code "4") (name "COMP") (class "Default")
      (node (ref "D3") (pin "A") (pinfunction "A_A") (pintype "passive"))
      (node (ref "D9") (pin "C") (pinfunction "C_C") (pintype "passive"))
      (node (ref "IC8") (pin "12") (pinfunction "+IN_12") (pintype "input"))
      (node (ref "IC8") (pin "6") (pinfunction "-IN_6") (pintype "input"))
      (node (ref "IC8") (pin "9") (pinfunction "-IN_9") (pintype "input"))
      (node (ref "R21") (pin "2") (pinfunction "2_2") (pintype "passive"))
      (node (ref "R33") (pin "1") (pinfunction "1_1") (pintype "passive"))
    )
    (net (code "5") (name "COMP_-12_+12") (class "Default")
      (node (ref "IC8") (pin "1") (pinfunction "OUT_1") (pintype "output"))
      (node (ref "R21") (pin "1") (pinfunction "1_1") (pintype "passive"))
    )
    (net (code "6") (name "FULL_WAVE_RECT") (class "Default")
      (node (ref "IC2") (pin "12") (pinfunction "+IN_12") (pintype "input"))
      (node (ref "IC2") (pin "8") (pinfunction "OUT_8") (pintype "output"))
      (node (ref "J7") (pin "P2") (pinfunction "2_P2") (pintype "passive"))
      (node (ref "R34") (pin "2") (pinfunction "2_2") (pintype "passive"))
      (node (ref "R36") (pin "1") (pinfunction "1_1") (pintype "passive"))
    )
    (net (code "7") (name "GND") (class "Default")
      (node (ref "C1") (pin "2") (pinfunction "2_2") (pintype "passive"))
      (node (ref "C12") (pin "1") (pinfunction "1_1") (pintype "passive"))
      (node (ref "C13") (pin "2") (pinfunction "2_2") (pintype "passive"))
      (node (ref "C14") (pin "2") (pinfunction "2_2") (pintype "passive"))
      (node (ref "C18") (pin "1") (pinfunction "1_1") (pintype "passive"))
      (node (ref "C19") (pin "2") (pinfunction "2_2") (pintype "passive"))
      (node (ref "C2") (pin "1") (pinfunction "1_1") (pintype "passive"))
      (node (ref "C20") (pin "1") (pinfunction "1_1") (pintype "passive"))
      (node (ref "C21") (pin "2") (pinfunction "2_2") (pintype "passive"))
      (node (ref "C22") (pin "2") (pinfunction "2_2") (pintype "passive"))
      (node (ref "C23") (pin "2") (pinfunction "2_2") (pintype "passive"))
      (node (ref "C24") (pin "1") (pinfunction "1_1") (pintype "passive"))
      (node (ref "C25") (pin "2") (pinfunction "2_2") (pintype "passive"))
      (node (ref "C26") (pin "1") (pinfunction "1_1") (pintype "passive"))
      (node (ref "C3") (pin "2") (pinfunction "2_2") (pintype "passive"))
      (node (ref "C4") (pin "1") (pinfunction "1_1") (pintype "passive"))
      (node (ref "C55") (pin "2") (pinfunction "2_2") (pintype "passive"))
      (node (ref "C56") (pin "2") (pinfunction "2_2") (pintype "passive"))
      (node (ref "C58") (pin "-") (pinfunction "-_-") (pintype "passive"))
      (node (ref "C6") (pin "2") (pinfunction "2_2") (pintype "passive"))
      (node (ref "C8") (pin "2") (pinfunction "2_2") (pintype "passive"))
      (node (ref "C9") (pin "2") (pinfunction "2_2") (pintype "passive"))
      (node (ref "IC3") (pin "10") (pinfunction "+IN_10") (pintype "input"))
      (node (ref "IC3") (pin "3") (pinfunction "+IN_3") (pintype "input"))
      (node (ref "IC3") (pin "6") (pinfunction "-IN_6") (pintype "input"))
      (node (ref "IC4") (pin "4") (pinfunction "V-_4") (pintype "power_in"))
      (node (ref "IC6") (pin "2") (pinfunction "A_2") (pintype "passive"))
      (node (ref "IC7") (pin "2") (pinfunction "A_2") (pintype "passive"))
      (node (ref "IC8") (pin "10") (pinfunction "+IN_10") (pintype "input"))
      (node (ref "J1") (pin "P1") (pinfunction "1_P1") (pintype "passive"))
      (node (ref "J10") (pin "P1") (pinfunction "1_P1") (pintype "passive"))
      (node (ref "J11") (pin "P1") (pinfunction "1_P1") (pintype "passive"))
      (node (ref "J12") (pin "P1") (pinfunction "1_P1") (pintype "passive"))
      (node (ref "J2") (pin "P1") (pinfunction "1_P1") (pintype "passive"))
      (node (ref "J3") (pin "P1") (pinfunction "1_P1") (pintype "passive"))
      (node (ref "J4") (pin "P1") (pinfunction "1_P1") (pintype "passive"))
      (node (ref "J5") (pin "P1") (pinfunction "1_P1") (pintype "passive"))
      (node (ref "J6") (pin "P1") (pinfunction "1_P1") (pintype "passive"))
      (node (ref "J7") (pin "P1") (pinfunction "1_P1") (pintype "passive"))
      (node (ref "J8") (pin "P1") (pinfunction "1_P1") (pintype "passive"))
      (node (ref "J9") (pin "P1") (pinfunction "1_P1") (pintype "passive"))
      (node (ref "JP4") (pin "3") (pinfunction "3_3") (pintype "passive"))
      (node (ref "JP4") (pin "4") (pinfunction "4_4") (pintype "passive"))
      (node (ref "JP4") (pin "5") (pinfunction "5_5") (pintype "passive"))
      (node (ref "JP4") (pin "6") (pinfunction "6_6") (pintype "passive"))
      (node (ref "JP4") (pin "7") (pinfunction "7_7") (pintype "passive"))
      (node (ref "JP4") (pin "8") (pinfunction "8_8") (pintype "passive"))
      (node (ref "LED1") (pin "K") (pinfunction "C_K") (pintype "passive"))
      (node (ref "Q1") (pin "E") (pinfunction "E_E") (pintype "passive"))
      (node (ref "R10") (pin "1") (pinfunction "1_1") (pintype "passive"))
      (node (ref "R116") (pin "1") (pinfunction "1_1") (pintype "passive"))
      (node (ref "R117") (pin "1") (pinfunction "1_1") (pintype "passive"))
      (node (ref "R120") (pin "1") (pinfunction "1_1") (pintype "passive"))
      (node (ref "R17") (pin "2") (pinfunction "2_2") (pintype "passive"))
      (node (ref "R30") (pin "1") (pinfunction "1_1") (pintype "passive"))
      (node (ref "R32") (pin "1") (pinfunction "1_1") (pintype "passive"))
      (node (ref "R5") (pin "1") (pinfunction "1_1") (pintype "passive"))
      (node (ref "R6") (pin "2") (pinfunction "2_2") (pintype "passive"))
      (node (ref "R8") (pin "2") (pinfunction "2_2") (pintype "passive"))
      (node (ref "R9") (pin "2") (pinfunction "2_2") (pintype "passive"))
    )
    (net (code "8") (name "LOWPASS") (class "Default")
      (node (ref "IC5") (pin "12") (pinfunction "+IN_12") (pintype "input"))
      (node (ref "IC5") (pin "8") (pinfunction "OUT_8") (pintype "output"))
      (node (ref "IC5") (pin "9") (pinfunction "-IN_9") (pintype "input"))
      (node (ref "J11") (pin "P2") (pinfunction "2_P2") (pintype "passive"))
      (node (ref "R23") (pin "1") (pinfunction "1_1") (pintype "passive"))
    )
    (net (code "9") (name "Net-(C5-Pad2)") (class "Default")
      (node (ref "C5") (pin "2") (pinfunction "2_2") (pintype "passive"))
      (node (ref "R4") (pin "2") (pinfunction "2_2") (pintype "passive"))
      (node (ref "R5") (pin "2") (pinfunction "2_2") (pintype "passive"))
      (node (ref "SJ1") (pin "2") (pinfunction "2_2") (pintype "passive"))
    )
    (net (code "10") (name "Net-(C8-Pad1)") (class "Default")
      (node (ref "C8") (pin "1") (pinfunction "1_1") (pintype "passive"))
      (node (ref "D4") (pin "C") (pinfunction "C_C") (pintype "passive"))
      (node (ref "R11") (pin "2") (pinfunction "2_2") (pintype "passive"))
    )
    (net (code "11") (name "Net-(C16-Pad2)") (class "Default")
      (node (ref "C16") (pin "2") (pinfunction "2_2") (pintype "passive"))
      (node (ref "R1") (pin "1") (pinfunction "1_1") (pintype "passive"))
      (node (ref "SJ2") (pin "2") (pinfunction "2_2") (pintype "passive"))
    )
    (net (code "12") (name "Net-(C17-Pad1)") (class "Default")
      (node (ref "C17") (pin "1") (pinfunction "1_1") (pintype "passive"))
      (node (ref "R22") (pin "2") (pinfunction "2_2") (pintype "passive"))
    )
    (net (code "13") (name "Net-(C55-Pad1)") (class "Default")
      (node (ref "C55") (pin "1") (pinfunction "1_1") (pintype "passive"))
      (node (ref "R113") (pin "2") (pinfunction "2_2") (pintype "passive"))
      (node (ref "R114") (pin "1") (pinfunction "1_1") (pintype "passive"))
    )
    (net (code "14") (name "Net-(C57-Pad1)") (class "Default")
      (node (ref "C57") (pin "1") (pinfunction "1_1") (pintype "passive"))
      (node (ref "R115") (pin "1") (pinfunction "1_1") (pintype "passive"))
    )
    (net (code "15") (name "Net-(D1-PadA)") (class "Default")
      (node (ref "D1") (pin "A") (pinfunction "A_A") (pintype "passive"))
      (node (ref "JP4") (pin "1") (pinfunction "1_1") (pintype "passive"))
      (node (ref "JP4") (pin "2") (pinfunction "2_2") (pintype "passive"))
    )
    (net (code "16") (name "Net-(D1-PadC)") (class "Default")
      (node (ref "D1") (pin "C") (pinfunction "C_C") (pintype "passive"))
      (node (ref "L1") (pin "2") (pinfunction "2_2") (pintype "passive"))
    )
    (net (code "17") (name "Net-(D2-PadA)") (class "Default")
      (node (ref "D2") (pin "A") (pinfunction "A_A") (pintype "passive"))
      (node (ref "L2") (pin "2") (pinfunction "2_2") (pintype "passive"))
    )
    (net (code "18") (name "Net-(D2-PadC)") (class "Default")
      (node (ref "D2") (pin "C") (pinfunction "C_C") (pintype "passive"))
      (node (ref "JP4") (pin "10") (pinfunction "10_10") (pintype "passive"))
      (node (ref "JP4") (pin "9") (pinfunction "9_9") (pintype "passive"))
    )
    (net (code "19") (name "Net-(D13-PadC)") (class "Default")
      (node (ref "D13") (pin "C") (pinfunction "C_C") (pintype "passive"))
      (node (ref "D14") (pin "C") (pinfunction "C_C") (pintype "passive"))
      (node (ref "R113") (pin "1") (pinfunction "1_1") (pintype "passive"))
    )
    (net (code "20") (name "Net-(IC1A-+IN)") (class "Default")
      (node (ref "IC1") (pin "3") (pinfunction "+IN_3") (pintype "input"))
      (node (ref "R4") (pin "1") (pinfunction "1_1") (pintype "passive"))
    )
    (net (code "21") (name "Net-(IC1A--IN)") (class "Default")
      (node (ref "C7") (pin "1") (pinfunction "1_1") (pintype "passive"))
      (node (ref "IC1") (pin "2") (pinfunction "-IN_2") (pintype "input"))
      (node (ref "R6") (pin "1") (pinfunction "1_1") (pintype "passive"))
      (node (ref "R7") (pin "P$2") (pinfunction "S_P$2") (pintype "passive"))
    )
    (net (code "22") (name "Net-(IC2A-+IN)") (class "Default")
      (node (ref "C17") (pin "2") (pinfunction "2_2") (pintype "passive"))
      (node (ref "IC2") (pin "3") (pinfunction "+IN_3") (pintype "input"))
    )
    (net (code "23") (name "Net-(IC2A--IN)") (class "Default")
      (node (ref "IC2") (pin "1") (pinfunction "OUT_1") (pintype "output"))
      (node (ref "IC2") (pin "2") (pinfunction "-IN_2") (pintype "input"))
      (node (ref "IC2") (pin "5") (pinfunction "+IN_5") (pintype "input"))
      (node (ref "R30") (pin "2") (pinfunction "2_2") (pintype "passive"))
    )
    (net (code "24") (name "Net-(IC2B--IN)") (class "Default")
      (node (ref "C15") (pin "1") (pinfunction "1_1") (pintype "passive"))
      (node (ref "D7") (pin "A") (pinfunction "A_A") (pintype "passive"))
      (node (ref "IC2") (pin "6") (pinfunction "-IN_6") (pintype "input"))
      (node (ref "R31") (pin "1") (pinfunction "1_1") (pintype "passive"))
    )
    (net (code "25") (name "Net-(IC2B-OUT)") (class "Default")
      (node (ref "C15") (pin "2") (pinfunction "2_2") (pintype "passive"))
      (node (ref "D7") (pin "C") (pinfunction "C_C") (pintype "passive"))
      (node (ref "D8") (pin "A") (pinfunction "A_A") (pintype "passive"))
      (node (ref "IC2") (pin "7") (pinfunction "OUT_7") (pintype "output"))
    )
    (net (code "26") (name "Net-(IC2C-+IN)") (class "Default")
      (node (ref "D8") (pin "C") (pinfunction "C_C") (pintype "passive"))
      (node (ref "IC2") (pin "10") (pinfunction "+IN_10") (pintype "input"))
      (node (ref "R32") (pin "2") (pinfunction "2_2") (pintype "passive"))
    )
    (net (code "27") (name "Net-(IC2C--IN)") (class "Default")
      (node (ref "IC2") (pin "9") (pinfunction "-IN_9") (pintype "input"))
      (node (ref "R31") (pin "2") (pinfunction "2_2") (pintype "passive"))
      (node (ref "R34") (pin "1") (pinfunction "1_1") (pintype "passive"))
    )
    (net (code "28") (name "Net-(IC2D-OUT)") (class "Default")
      (node (ref "D4") (pin "A") (pinfunction "A_A") (pintype "passive"))
      (node (ref "IC2") (pin "14") (pinfunction "OUT_14") (pintype "output"))
    )
    (net (code "29") (name "Net-(IC3A--IN)") (class "Default")
      (node (ref "IC3") (pin "2") (pinfunction "-IN_2") (pintype "input"))
      (node (ref "R25") (pin "2") (pinfunction "2_2") (pintype "passive"))
      (node (ref "R29") (pin "1") (pinfunction "1_1") (pintype "passive"))
    )
    (net (code "30") (name "Net-(IC3A-OUT)") (class "Default")
      (node (ref "IC3") (pin "1") (pinfunction "OUT_1") (pintype "output"))
      (node (ref "R26") (pin "1") (pinfunction "1_1") (pintype "passive"))
      (node (ref "R29") (pin "2") (pinfunction "2_2") (pintype "passive"))
    )
    (net (code "31") (name "Net-(IC3B-+IN)") (class "Default")
      (node (ref "IC3") (pin "5") (pinfunction "+IN_5") (pintype "input"))
      (node (ref "R26") (pin "2") (pinfunction "2_2") (pintype "passive"))
      (node (ref "R28") (pin "1") (pinfunction "1_1") (pintype "passive"))
    )
    (net (code "32") (name "Net-(IC3B-OUT)") (class "Default")
      (node (ref "D5") (pin "A") (pinfunction "A_A") (pintype "passive"))
      (node (ref "D6") (pin "C") (pinfunction "C_C") (pintype "passive"))
      (node (ref "IC3") (pin "7") (pinfunction "OUT_7") (pintype "output"))
    )
    (net (code "33") (name "Net-(IC3C--IN)") (class "Default")
      (node (ref "C11") (pin "1") (pinfunction "1_1") (pintype "passive"))
      (node (ref "IC3") (pin "9") (pinfunction "-IN_9") (pintype "input"))
      (node (ref "R18") (pin "P$2") (pinfunction "S_P$2") (pintype "passive"))
      (node (ref "R19") (pin "P$2") (pinfunction "S_P$2") (pintype "passive"))
    )
    (net (code "34") (name "Net-(IC3D-+IN)") (class "Default")
      (node (ref "IC3") (pin "12") (pinfunction "+IN_12") (pintype "input"))
      (node (ref "R13") (pin "2") (pinfunction "2_2") (pintype "passive"))
    )
    (net (code "35") (name "Net-(IC3D--IN)") (class "Default")
      (node (ref "IC3") (pin "13") (pinfunction "-IN_13") (pintype "input"))
      (node (ref "IC3") (pin "14") (pinfunction "OUT_14") (pintype "output"))
      (node (ref "R25") (pin "1") (pinfunction "1_1") (pintype "passive"))
    )
    (net (code "36") (name "Net-(IC4A-+IN)") (class "Default")
      (node (ref "IC4") (pin "3") (pinfunction "+IN_3") (pintype "input"))
      (node (ref "IC4") (pin "6") (pinfunction "-IN_6") (pintype "input"))
      (node (ref "R115") (pin "2") (pinfunction "2_2") (pintype "passive"))
      (node (ref "R117") (pin "2") (pinfunction "2_2") (pintype "passive"))
      (node (ref "R118") (pin "1") (pinfunction "1_1") (pintype "passive"))
    )
    (net (code "37") (name "Net-(IC4A--IN)") (class "Default")
      (node (ref "IC4") (pin "2") (pinfunction "-IN_2") (pintype "input"))
      (node (ref "R119") (pin "2") (pinfunction "2_2") (pintype "passive"))
      (node (ref "R121") (pin "1") (pinfunction "1_1") (pintype "passive"))
    )
    (net (code "38") (name "Net-(IC4A-OUT)") (class "Default")
      (node (ref "D13") (pin "A") (pinfunction "A_A") (pintype "passive"))
      (node (ref "IC4") (pin "1") (pinfunction "OUT_1") (pintype "output"))
    )
    (net (code "39") (name "Net-(IC4B-+IN)") (class "Default")
      (node (ref "IC4") (pin "5") (pinfunction "+IN_5") (pintype "input"))
      (node (ref "R119") (pin "1") (pinfunction "1_1") (pintype "passive"))
      (node (ref "R120") (pin "2") (pinfunction "2_2") (pintype "passive"))
    )
    (net (code "40") (name "Net-(IC4B-OUT)") (class "Default")
      (node (ref "D14") (pin "A") (pinfunction "A_A") (pintype "passive"))
      (node (ref "IC4") (pin "7") (pinfunction "OUT_7") (pintype "output"))
    )
    (net (code "41") (name "Net-(IC5A--IN)") (class "Default")
      (node (ref "IC5") (pin "2") (pinfunction "-IN_2") (pintype "input"))
      (node (ref "LED3") (pin "K") (pinfunction "C_K") (pintype "passive"))
      (node (ref "R10") (pin "2") (pinfunction "2_2") (pintype "passive"))
    )
    (net (code "42") (name "Net-(IC5A-OUT)") (class "Default")
      (node (ref "IC5") (pin "1") (pinfunction "OUT_1") (pintype "output"))
      (node (ref "LED3") (pin "A") (pinfunction "A_A") (pintype "passive"))
    )
    (net (code "43") (name "Net-(IC5B-+IN)") (class "Default")
      (node (ref "IC5") (pin "5") (pinfunction "+IN_5") (pintype "input"))
      (node (ref "R14") (pin "2") (pinfunction "2_2") (pintype "passive"))
    )
    (net (code "44") (name "Net-(IC5B--IN)") (class "Default")
      (node (ref "IC5") (pin "6") (pinfunction "-IN_6") (pintype "input"))
      (node (ref "IC5") (pin "7") (pinfunction "OUT_7") (pintype "output"))
      (node (ref "R12") (pin "P$2") (pinfunction "S_P$2") (pintype "passive"))
    )
    (net (code "45") (name "Net-(IC5C-+IN)") (class "Default")
      (node (ref "C21") (pin "1") (pinfunction "1_1") (pintype "passive"))
      (node (ref "IC5") (pin "10") (pinfunction "+IN_10") (pintype "input"))
      (node (ref "R12") (pin "P$3") (pinfunction "A_P$3") (pintype "passive"))
    )
    (net (code "46") (name "Net-(IC5D--IN)") (class "Default")
      (node (ref "IC5") (pin "13") (pinfunction "-IN_13") (pintype "input"))
      (node (ref "LED2") (pin "K") (pinfunction "C_K") (pintype "passive"))
      (node (ref "R9") (pin "1") (pinfunction "1_1") (pintype "passive"))
    )
    (net (code "47") (name "Net-(IC5D-OUT)") (class "Default")
      (node (ref "IC5") (pin "14") (pinfunction "OUT_14") (pintype "output"))
      (node (ref "LED2") (pin "A") (pinfunction "A_A") (pintype "passive"))
    )
    (net (code "48") (name "Net-(IC8A-+IN)") (class "Default")
      (node (ref "IC8") (pin "3") (pinfunction "+IN_3") (pintype "input"))
      (node (ref "R15") (pin "2") (pinfunction "2_2") (pintype "passive"))
    )
    (net (code "49") (name "Net-(IC8A--IN)") (class "Default")
      (node (ref "IC8") (pin "2") (pinfunction "-IN_2") (pintype "input"))
      (node (ref "R16") (pin "2") (pinfunction "2_2") (pintype "passive"))
    )
    (net (code "50") (name "Net-(IC8B-OUT)") (class "Default")
      (node (ref "D3") (pin "C") (pinfunction "C_C") (pintype "passive"))
      (node (ref "IC8") (pin "7") (pinfunction "OUT_7") (pintype "output"))
    )
    (net (code "51") (name "Net-(IC8C-OUT)") (class "Default")
      (node (ref "D9") (pin "A") (pinfunction "A_A") (pintype "passive"))
      (node (ref "IC8") (pin "8") (pinfunction "OUT_8") (pintype "output"))
    )
    (net (code "52") (name "Net-(IC8D--IN)") (class "Default")
      (node (ref "IC8") (pin "13") (pinfunction "-IN_13") (pintype "input"))
      (node (ref "LED5") (pin "K") (pinfunction "C_K") (pintype "passive"))
      (node (ref "R17") (pin "1") (pinfunction "1_1") (pintype "passive"))
    )
    (net (code "53") (name "Net-(IC8D-OUT)") (class "Default")
      (node (ref "IC8") (pin "14") (pinfunction "OUT_14") (pintype "output"))
      (node (ref "LED5") (pin "A") (pinfunction "A_A") (pintype "passive"))
    )
    (net (code "54") (name "Net-(IC9A-+IN)") (class "Default")
      (node (ref "IC9") (pin "3") (pinfunction "+IN_3") (pintype "input"))
      (node (ref "R24") (pin "P$2") (pinfunction "S_P$2") (pintype "passive"))
    )
    (net (code "55") (name "Net-(J1-3)") (class "Default")
      (node (ref "C3") (pin "1") (pinfunction "1_1") (pintype "passive"))
      (node (ref "C5") (pin "1") (pinfunction "1_1") (pintype "passive"))
      (node (ref "J1") (pin "P3") (pinfunction "3_P3") (pintype "passive"))
      (node (ref "SJ1") (pin "1") (pinfunction "1_1") (pintype "passive"))
    )
    (net (code "56") (name "Net-(J2-3)") (class "Default")
      (node (ref "J2") (pin "P3") (pinfunction "3_P3") (pintype "passive"))
      (node (ref "R1") (pin "2") (pinfunction "2_2") (pintype "passive"))
    )
    (net (code "57") (name "Net-(J3-3)") (class "Default")
      (node (ref "J3") (pin "P3") (pinfunction "3_P3") (pintype "passive"))
      (node (ref "R2") (pin "2") (pinfunction "2_2") (pintype "passive"))
    )
    (net (code "58") (name "Net-(J4-3)") (class "Default")
      (node (ref "J4") (pin "P3") (pinfunction "3_P3") (pintype "passive"))
      (node (ref "R23") (pin "2") (pinfunction "2_2") (pintype "passive"))
    )
    (net (code "59") (name "Net-(J5-3)") (class "Default")
      (node (ref "J5") (pin "P3") (pinfunction "3_P3") (pintype "passive"))
      (node (ref "R36") (pin "2") (pinfunction "2_2") (pintype "passive"))
    )
    (net (code "60") (name "Net-(J6-3)") (class "Default")
      (node (ref "J6") (pin "P3") (pinfunction "3_P3") (pintype "passive"))
      (node (ref "R22") (pin "1") (pinfunction "1_1") (pintype "passive"))
    )
    (net (code "61") (name "Net-(J7-3)") (class "Default")
      (node (ref "J7") (pin "P3") (pinfunction "3_P3") (pintype "passive"))
      (node (ref "R13") (pin "1") (pinfunction "1_1") (pintype "passive"))
    )
    (net (code "62") (name "Net-(J8-3)") (class "Default")
      (node (ref "J8") (pin "P3") (pinfunction "3_P3") (pintype "passive"))
      (node (ref "R14") (pin "1") (pinfunction "1_1") (pintype "passive"))
    )
    (net (code "63") (name "Net-(J9-3)") (class "Default")
      (node (ref "J9") (pin "P3") (pinfunction "3_P3") (pintype "passive"))
      (node (ref "R33") (pin "2") (pinfunction "2_2") (pintype "passive"))
    )
    (net (code "64") (name "Net-(J10-3)") (class "Default")
      (node (ref "J10") (pin "P3") (pinfunction "3_P3") (pintype "passive"))
      (node (ref "R16") (pin "1") (pinfunction "1_1") (pintype "passive"))
    )
    (net (code "65") (name "Net-(J11-3)") (class "Default")
      (node (ref "J11") (pin "P3") (pinfunction "3_P3") (pintype "passive"))
      (node (ref "R15") (pin "1") (pinfunction "1_1") (pintype "passive"))
    )
    (net (code "66") (name "Net-(J12-3)") (class "Default")
      (node (ref "J12") (pin "P3") (pinfunction "3_P3") (pintype "passive"))
      (node (ref "R27") (pin "2") (pinfunction "2_2") (pintype "passive"))
    )
    (net (code "67") (name "Net-(LED1-PadA)") (class "Default")
      (node (ref "LED1") (pin "A") (pinfunction "A_A") (pintype "passive"))
      (node (ref "R11") (pin "1") (pinfunction "1_1") (pintype "passive"))
    )
    (net (code "68") (name "Net-(LED4-C)") (class "Default")
      (node (ref "LED4") (pin "K") (pinfunction "C_K") (pintype "passive"))
      (node (ref "Q1") (pin "C") (pinfunction "C_C") (pintype "passive"))
    )
    (net (code "69") (name "Net-(LED4-PadA)") (class "Default")
      (node (ref "LED4") (pin "A") (pinfunction "A_A") (pintype "passive"))
      (node (ref "R112") (pin "1") (pinfunction "1_1") (pintype "passive"))
    )
    (net (code "70") (name "Net-(Q1-PadB)") (class "Default")
      (node (ref "Q1") (pin "B") (pinfunction "B_B") (pintype "passive"))
      (node (ref "R114") (pin "2") (pinfunction "2_2") (pintype "passive"))
      (node (ref "R116") (pin "2") (pinfunction "2_2") (pintype "passive"))
    )
    (net (code "71") (name "Net-(R7-E)") (class "Default")
      (node (ref "R7") (pin "P$1") (pinfunction "E_P$1") (pintype "passive"))
      (node (ref "R8") (pin "1") (pinfunction "1_1") (pintype "passive"))
    )
    (net (code "72") (name "Net-(R18-A)") (class "Default")
      (node (ref "D6") (pin "A") (pinfunction "A_A") (pintype "passive"))
      (node (ref "R18") (pin "P$3") (pinfunction "A_P$3") (pintype "passive"))
    )
    (net (code "73") (name "Net-(R19-A)") (class "Default")
      (node (ref "D5") (pin "C") (pinfunction "C_C") (pintype "passive"))
      (node (ref "R19") (pin "P$3") (pinfunction "A_P$3") (pintype "passive"))
    )
    (net (code "74") (name "SLEW") (class "Default")
      (node (ref "C10") (pin "2") (pinfunction "2_2") (pintype "passive"))
      (node (ref "C11") (pin "2") (pinfunction "2_2") (pintype "passive"))
      (node (ref "IC3") (pin "8") (pinfunction "OUT_8") (pintype "output"))
      (node (ref "IC5") (pin "3") (pinfunction "+IN_3") (pintype "input"))
      (node (ref "J8") (pin "P2") (pinfunction "2_P2") (pintype "passive"))
      (node (ref "R2") (pin "1") (pinfunction "1_1") (pintype "passive"))
      (node (ref "R28") (pin "2") (pinfunction "2_2") (pintype "passive"))
    )
    (net (code "75") (name "THRESH") (class "Default")
      (node (ref "IC9") (pin "1") (pinfunction "OUT_1") (pintype "output"))
      (node (ref "IC9") (pin "2") (pinfunction "-IN_2") (pintype "input"))
      (node (ref "J10") (pin "P2") (pinfunction "2_P2") (pintype "passive"))
      (node (ref "R27") (pin "1") (pinfunction "1_1") (pintype "passive"))
    )
    (net (code "76") (name "VCC") (class "Default")
      (node (ref "C1") (pin "1") (pinfunction "1_1") (pintype "passive"))
      (node (ref "C13") (pin "1") (pinfunction "1_1") (pintype "passive"))
      (node (ref "C19") (pin "1") (pinfunction "1_1") (pintype "passive"))
      (node (ref "C23") (pin "1") (pinfunction "1_1") (pintype "passive"))
      (node (ref "C25") (pin "1") (pinfunction "1_1") (pintype "passive"))
      (node (ref "C56") (pin "1") (pinfunction "1_1") (pintype "passive"))
      (node (ref "C58") (pin "+") (pinfunction "+_+") (pintype "passive"))
      (node (ref "C6") (pin "1") (pinfunction "1_1") (pintype "passive"))
      (node (ref "C9") (pin "1") (pinfunction "1_1") (pintype "passive"))
      (node (ref "IC1") (pin "7") (pinfunction "V+_7") (pintype "power_in"))
      (node (ref "IC2") (pin "4") (pinfunction "V+_4") (pintype "power_in"))
      (node (ref "IC3") (pin "4") (pinfunction "V+_4") (pintype "power_in"))
      (node (ref "IC4") (pin "8") (pinfunction "V+_8") (pintype "power_in"))
      (node (ref "IC5") (pin "4") (pinfunction "V+_4") (pintype "power_in"))
      (node (ref "IC8") (pin "4") (pinfunction "V+_4") (pintype "power_in"))
      (node (ref "IC9") (pin "4") (pinfunction "V+_4") (pintype "power_in"))
      (node (ref "L1") (pin "1") (pinfunction "1_1") (pintype "passive"))
      (node (ref "R112") (pin "2") (pinfunction "2_2") (pintype "passive"))
      (node (ref "R20") (pin "1") (pinfunction "1_1") (pintype "passive"))
      (node (ref "R3") (pin "1") (pinfunction "1_1") (pintype "passive"))
    )
    (net (code "77") (name "VEE") (class "Default")
      (node (ref "C12") (pin "2") (pinfunction "2_2") (pintype "passive"))
      (node (ref "C18") (pin "2") (pinfunction "2_2") (pintype "passive"))
      (node (ref "C2") (pin "2") (pinfunction "2_2") (pintype "passive"))
      (node (ref "C20") (pin "2") (pinfunction "2_2") (pintype "passive"))
      (node (ref "C24") (pin "2") (pinfunction "2_2") (pintype "passive"))
      (node (ref "C26") (pin "2") (pinfunction "2_2") (pintype "passive"))
      (node (ref "C4") (pin "2") (pinfunction "2_2") (pintype "passive"))
      (node (ref "IC1") (pin "4") (pinfunction "V-_4") (pintype "power_in"))
      (node (ref "IC2") (pin "11") (pinfunction "V-_11") (pintype "power_in"))
      (node (ref "IC3") (pin "11") (pinfunction "V-_11") (pintype "power_in"))
      (node (ref "IC5") (pin "11") (pinfunction "V-_11") (pintype "power_in"))
      (node (ref "IC8") (pin "11") (pinfunction "V-_11") (pintype "power_in"))
      (node (ref "IC9") (pin "11") (pinfunction "V-_11") (pintype "power_in"))
      (node (ref "L2") (pin "1") (pinfunction "1_1") (pintype "passive"))
    )
    (net (code "78") (name "unconnected-(C10-Pad1)") (class "Default")
      (node (ref "C10") (pin "1") (pinfunction "1_1") (pintype "passive"))
    )
    (net (code "79") (name "unconnected-(IC9B-+IN-Pad5)") (class "Default")
      (node (ref "IC9") (pin "5") (pinfunction "+IN_5") (pintype "input"))
    )
    (net (code "80") (name "unconnected-(IC9B--IN-Pad6)") (class "Default")
      (node (ref "IC9") (pin "6") (pinfunction "-IN_6") (pintype "input"))
    )
    (net (code "81") (name "unconnected-(IC9B-OUT-Pad7)") (class "Default")
      (node (ref "IC9") (pin "7") (pinfunction "OUT_7") (pintype "output"))
    )
    (net (code "82") (name "unconnected-(IC9C-+IN-Pad10)") (class "Default")
      (node (ref "IC9") (pin "10") (pinfunction "+IN_10") (pintype "input"))
    )
    (net (code "83") (name "unconnected-(IC9C--IN-Pad9)") (class "Default")
      (node (ref "IC9") (pin "9") (pinfunction "-IN_9") (pintype "input"))
    )
    (net (code "84") (name "unconnected-(IC9C-OUT-Pad8)") (class "Default")
      (node (ref "IC9") (pin "8") (pinfunction "OUT_8") (pintype "output"))
    )
    (net (code "85") (name "unconnected-(IC9D-+IN-Pad12)") (class "Default")
      (node (ref "IC9") (pin "12") (pinfunction "+IN_12") (pintype "input"))
    )
    (net (code "86") (name "unconnected-(IC9D--IN-Pad13)") (class "Default")
      (node (ref "IC9") (pin "13") (pinfunction "-IN_13") (pintype "input"))
    )
    (net (code "87") (name "unconnected-(IC9D-OUT-Pad14)") (class "Default")
      (node (ref "IC9") (pin "14") (pinfunction "OUT_14") (pintype "output"))
    )
    (net (code "88") (name "unconnected-(J1-2-PadP2)") (class "Default")
      (node (ref "J1") (pin "P2") (pinfunction "2_P2") (pintype "passive"))
    )
    (net (code "89") (name "unconnected-(J2-2-PadP2)") (class "Default")
      (node (ref "J2") (pin "P2") (pinfunction "2_P2") (pintype "passive"))
    )
    (net (code "90") (name "unconnected-(J3-2-PadP2)") (class "Default")
      (node (ref "J3") (pin "P2") (pinfunction "2_P2") (pintype "passive"))
    )
    (net (code "91") (name "unconnected-(J4-2-PadP2)") (class "Default")
      (node (ref "J4") (pin "P2") (pinfunction "2_P2") (pintype "passive"))
    )
    (net (code "92") (name "unconnected-(J5-2-PadP2)") (class "Default")
      (node (ref "J5") (pin "P2") (pinfunction "2_P2") (pintype "passive"))
    )
    (net (code "93") (name "unconnected-(J9-2-PadP2)") (class "Default")
      (node (ref "J9") (pin "P2") (pinfunction "2_P2") (pintype "passive"))
    )
    (net (code "94") (name "unconnected-(J12-2-PadP2)") (class "Default")
      (node (ref "J12") (pin "P2") (pinfunction "2_P2") (pintype "passive"))
    )
    (net (code "95") (name "unconnected-(R12-E-PadP$1)") (class "Default")
      (node (ref "R12") (pin "P$1") (pinfunction "E_P$1") (pintype "passive"))
    )
    (net (code "96") (name "unconnected-(R18-E-PadP$1)") (class "Default")
      (node (ref "R18") (pin "P$1") (pinfunction "E_P$1") (pintype "passive"))
    )
    (net (code "97") (name "unconnected-(R19-E-PadP$1)") (class "Default")
      (node (ref "R19") (pin "P$1") (pinfunction "E_P$1") (pintype "passive"))
    )
    (net (code "98") (name "unconnected-(R24-E-PadP$1)") (class "Default")
      (node (ref "R24") (pin "P$1") (pinfunction "E_P$1") (pintype "passive"))
    )
  )
)
